# AJH_sup_marbles_v70.net
KiCad netlist of a schematic drawn in EAGLE
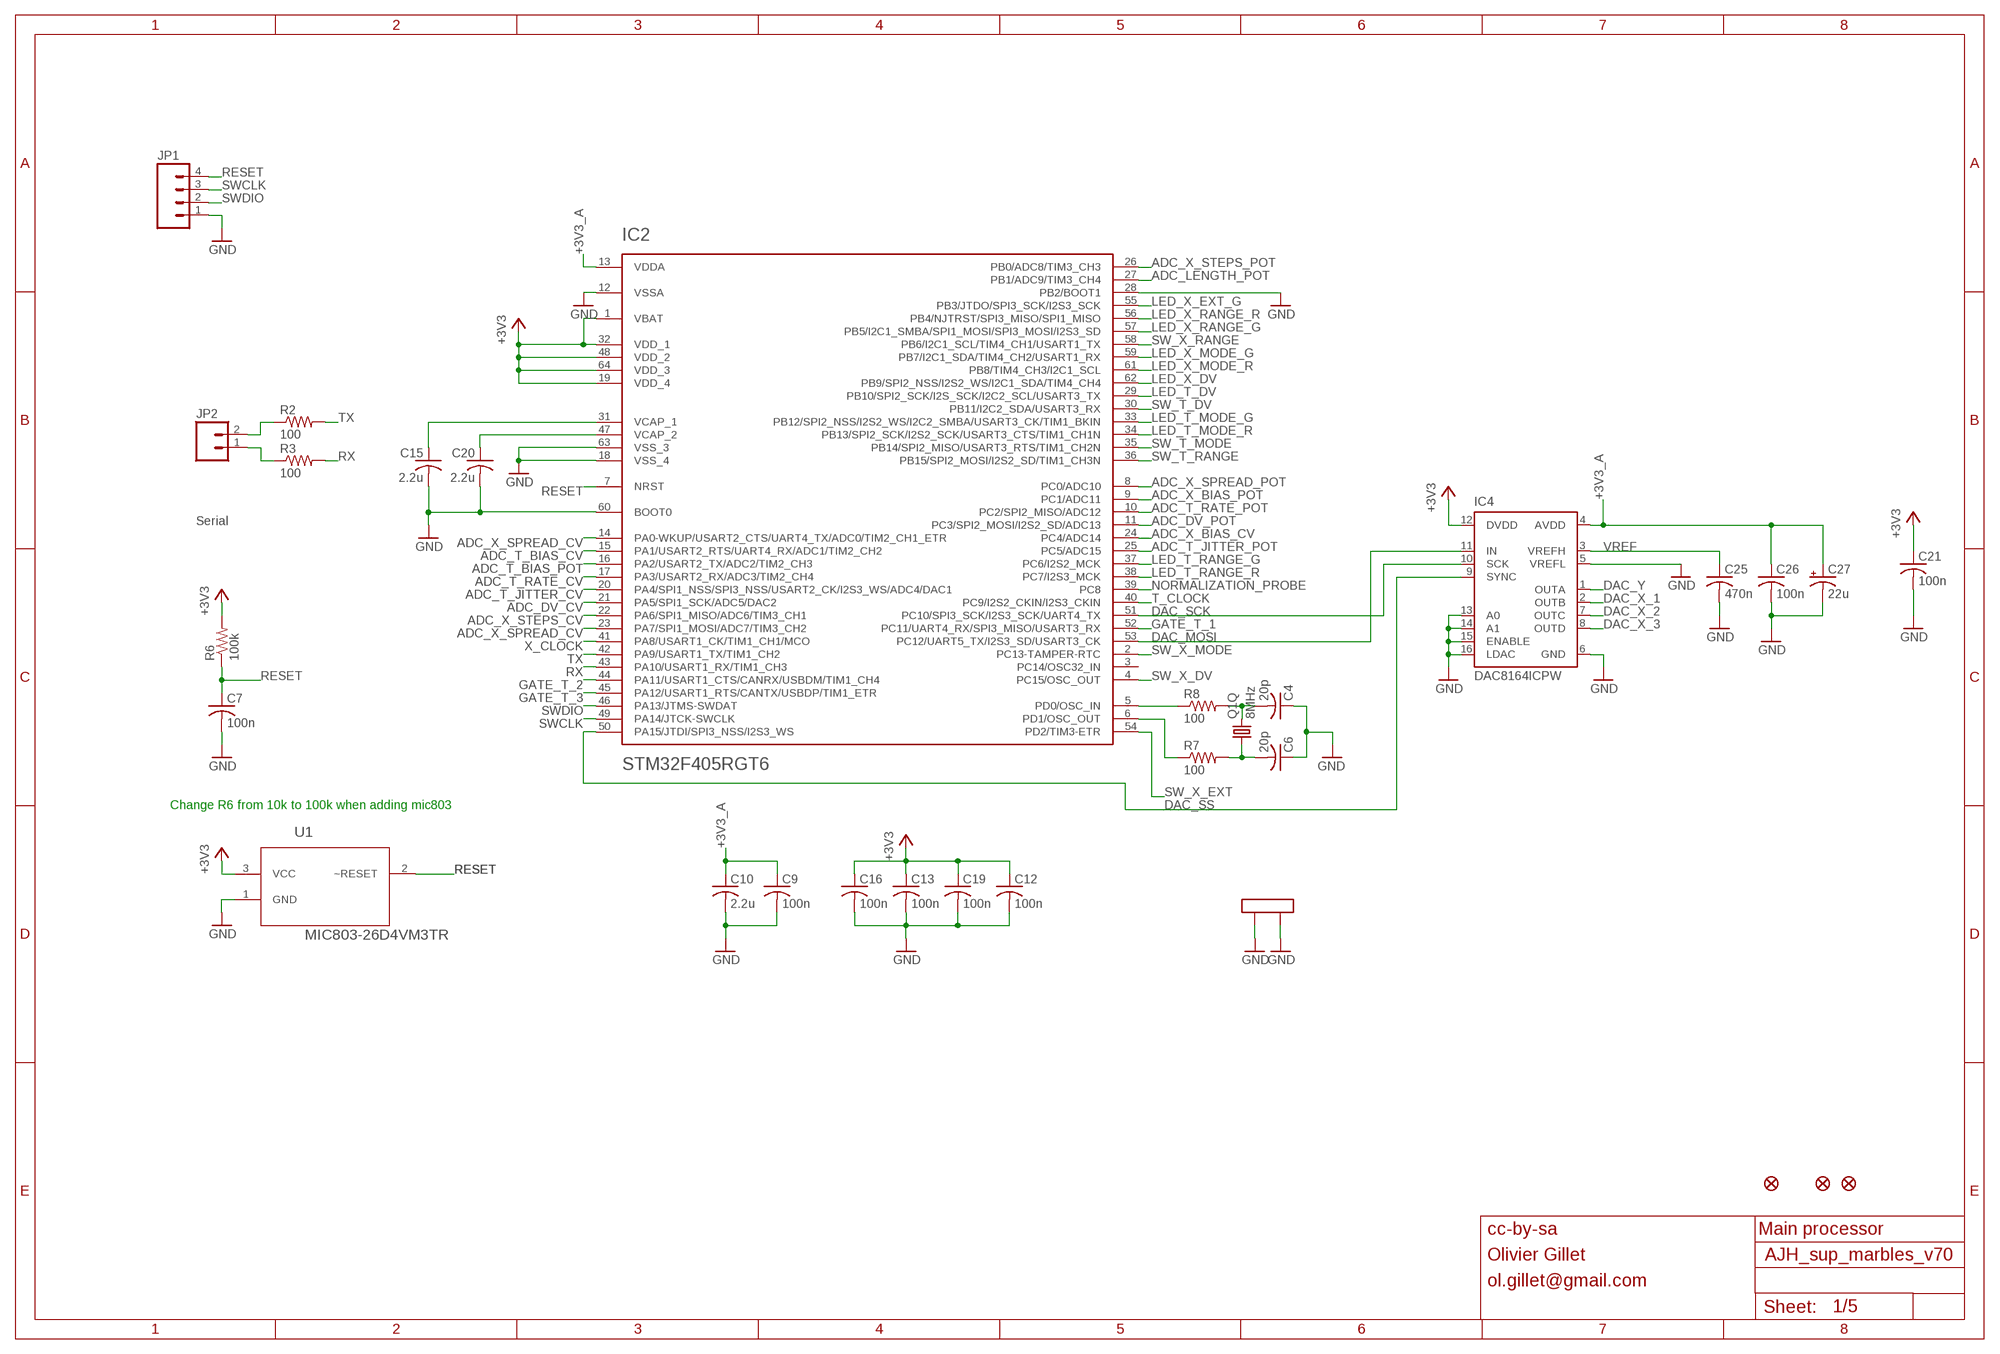
[diagram p0: schematic, sheet 1]
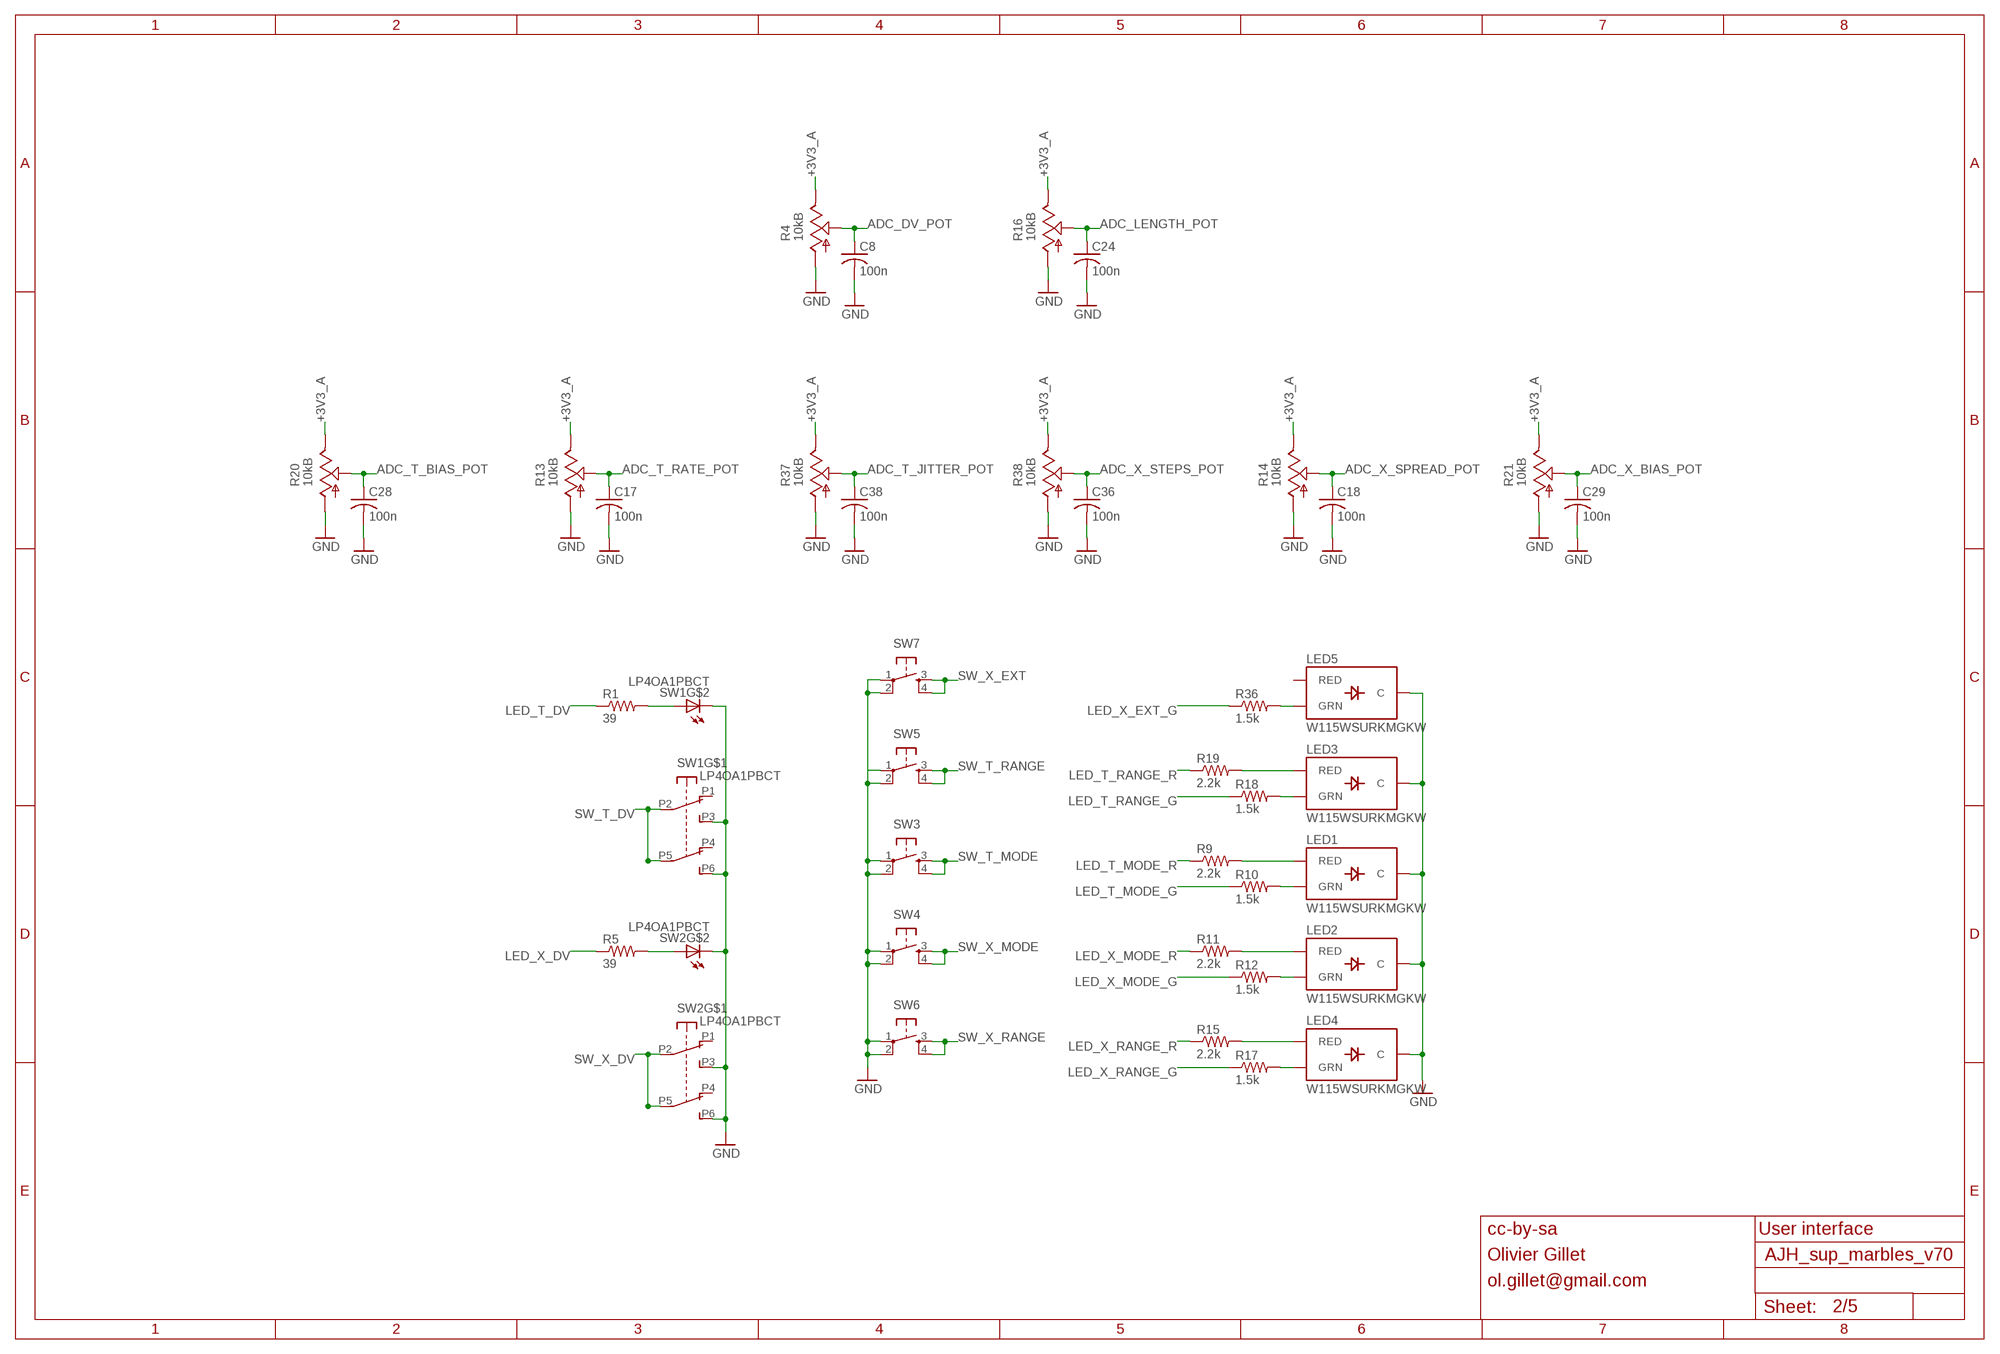
[diagram p1: schematic, sheet 2]
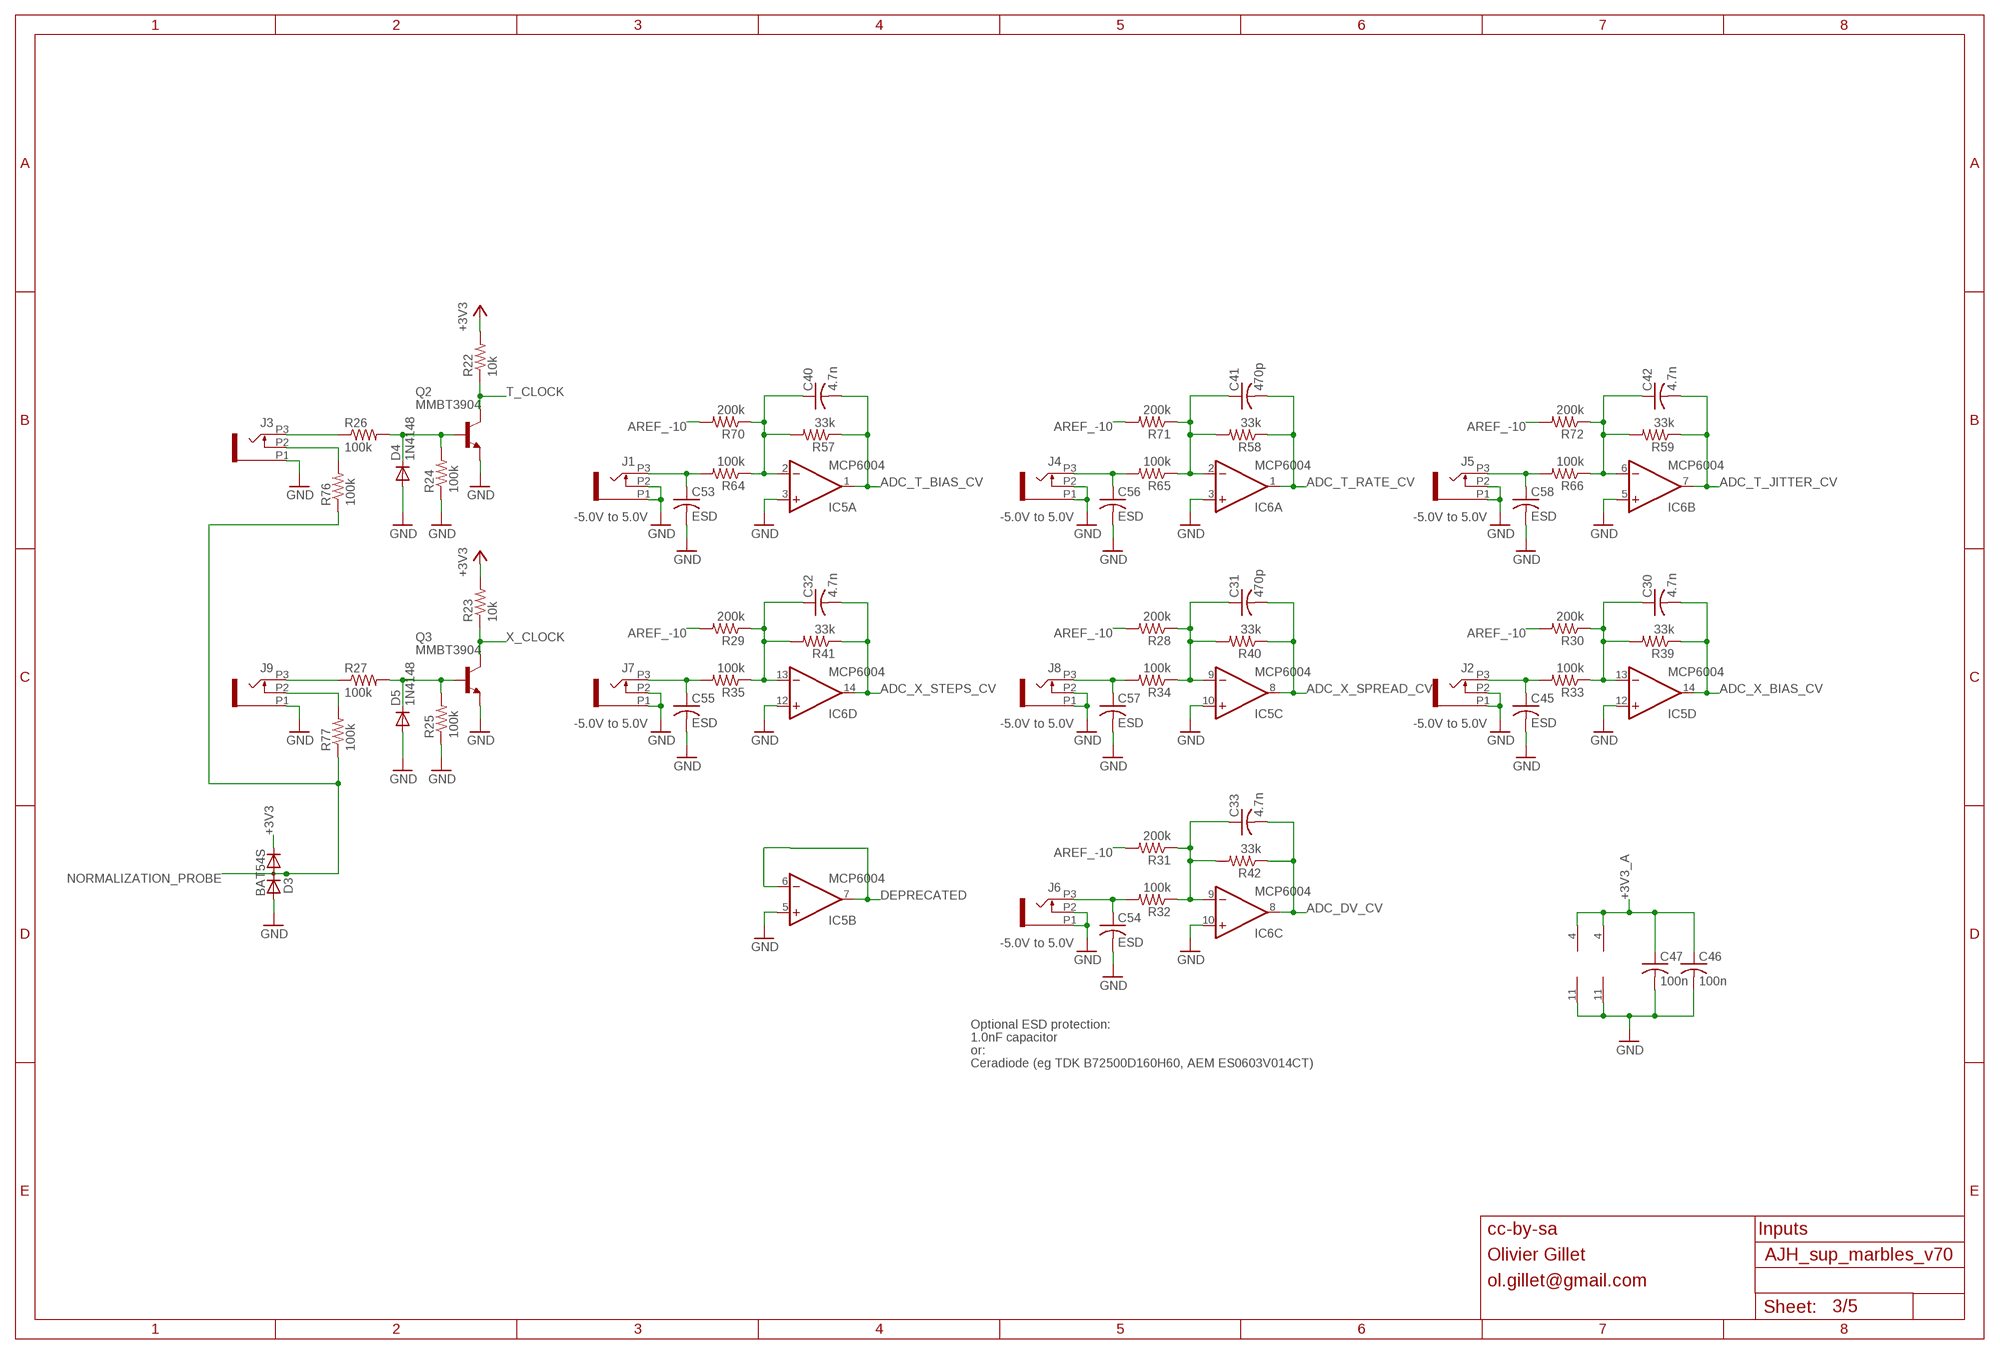
[diagram p2: schematic, sheet 3]
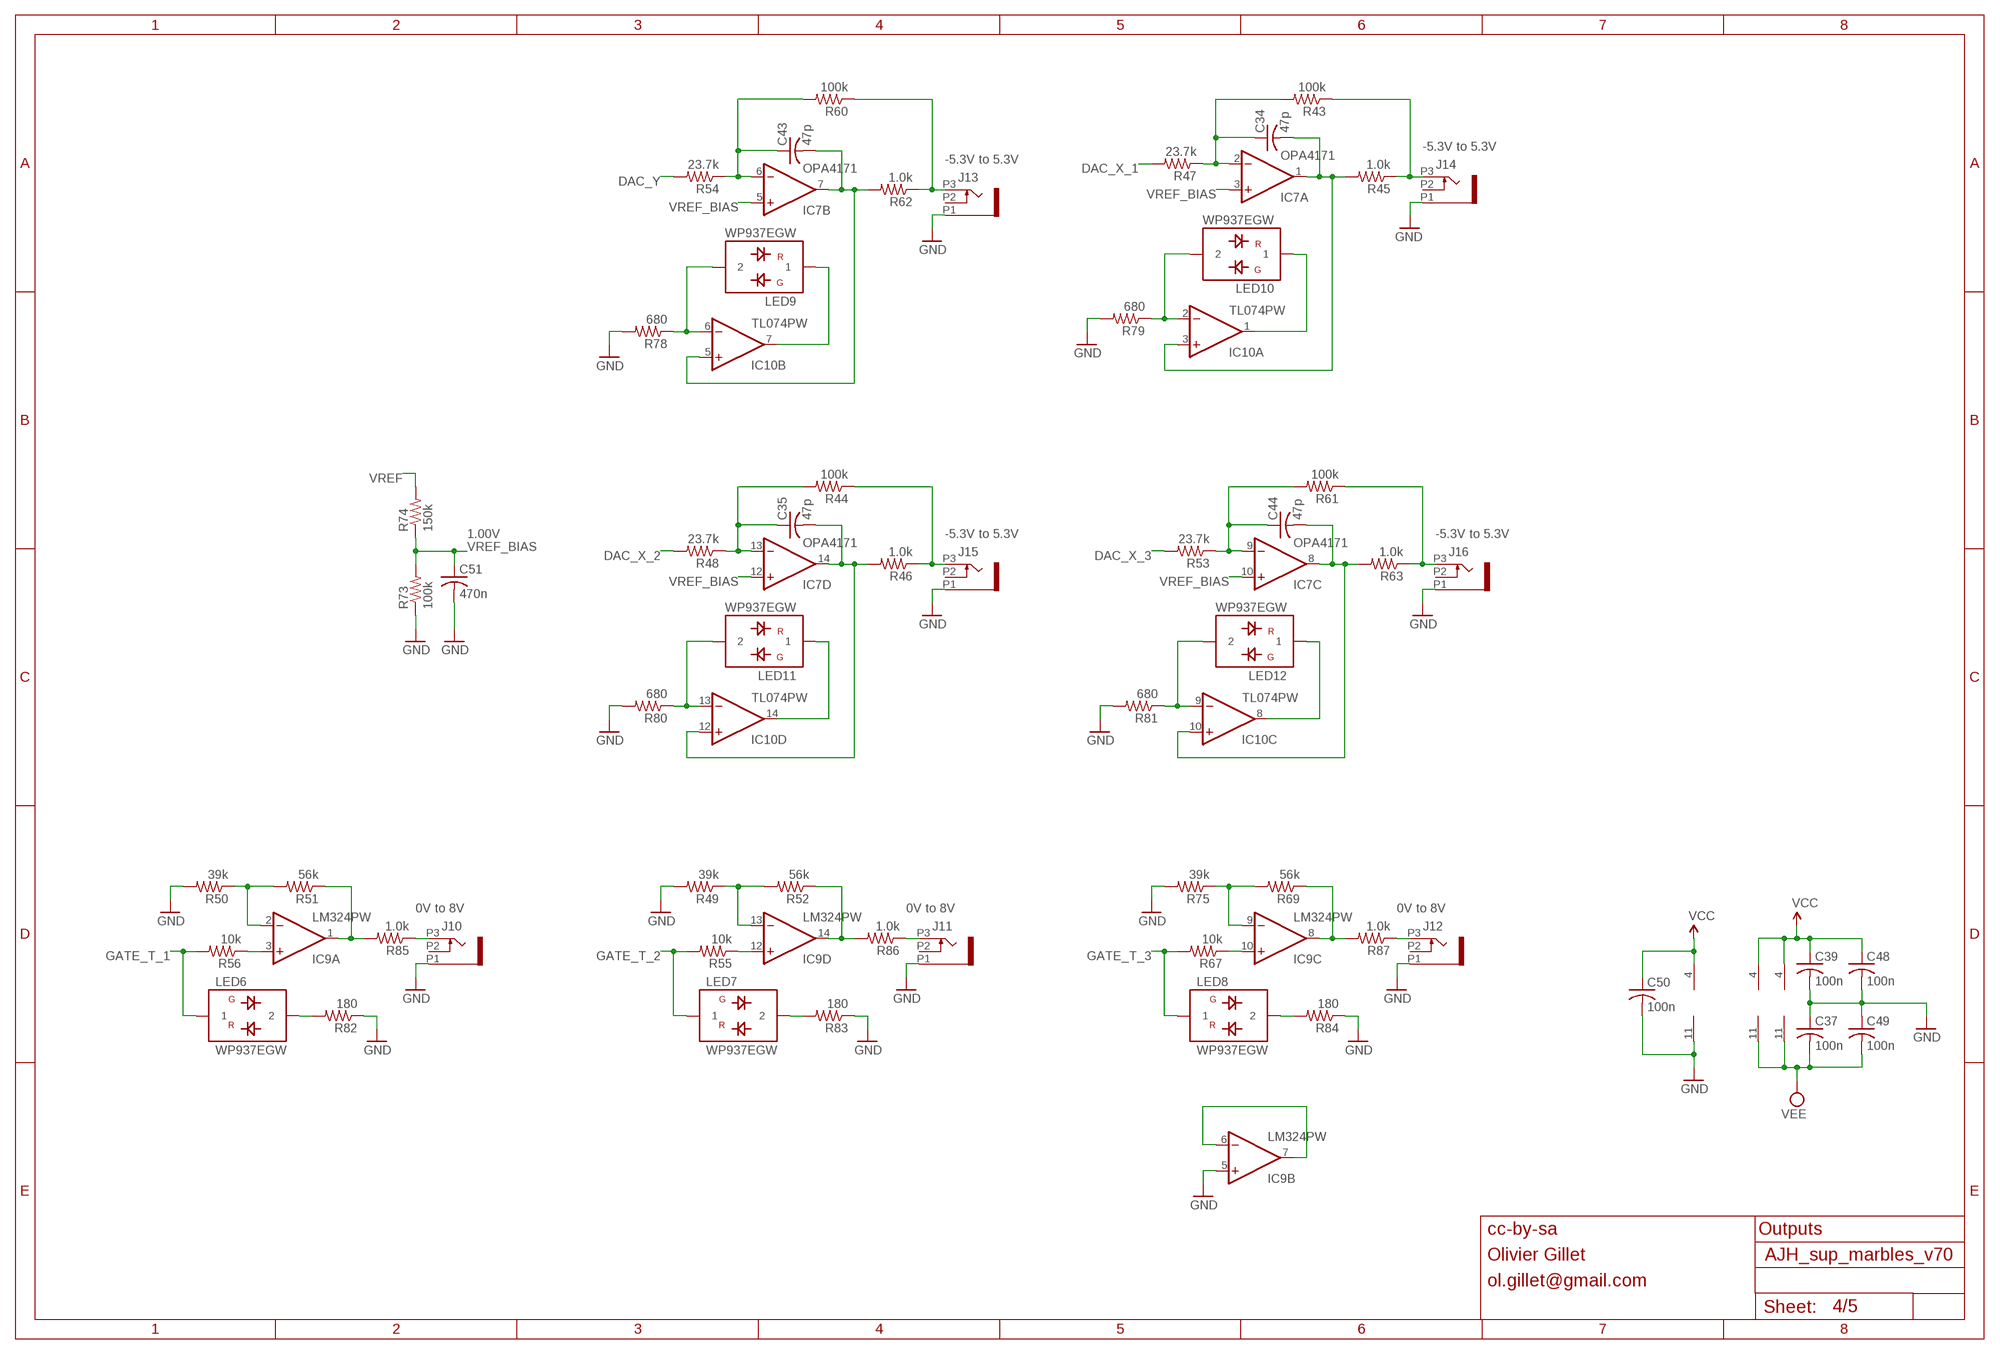
[diagram p3: schematic, sheet 4]
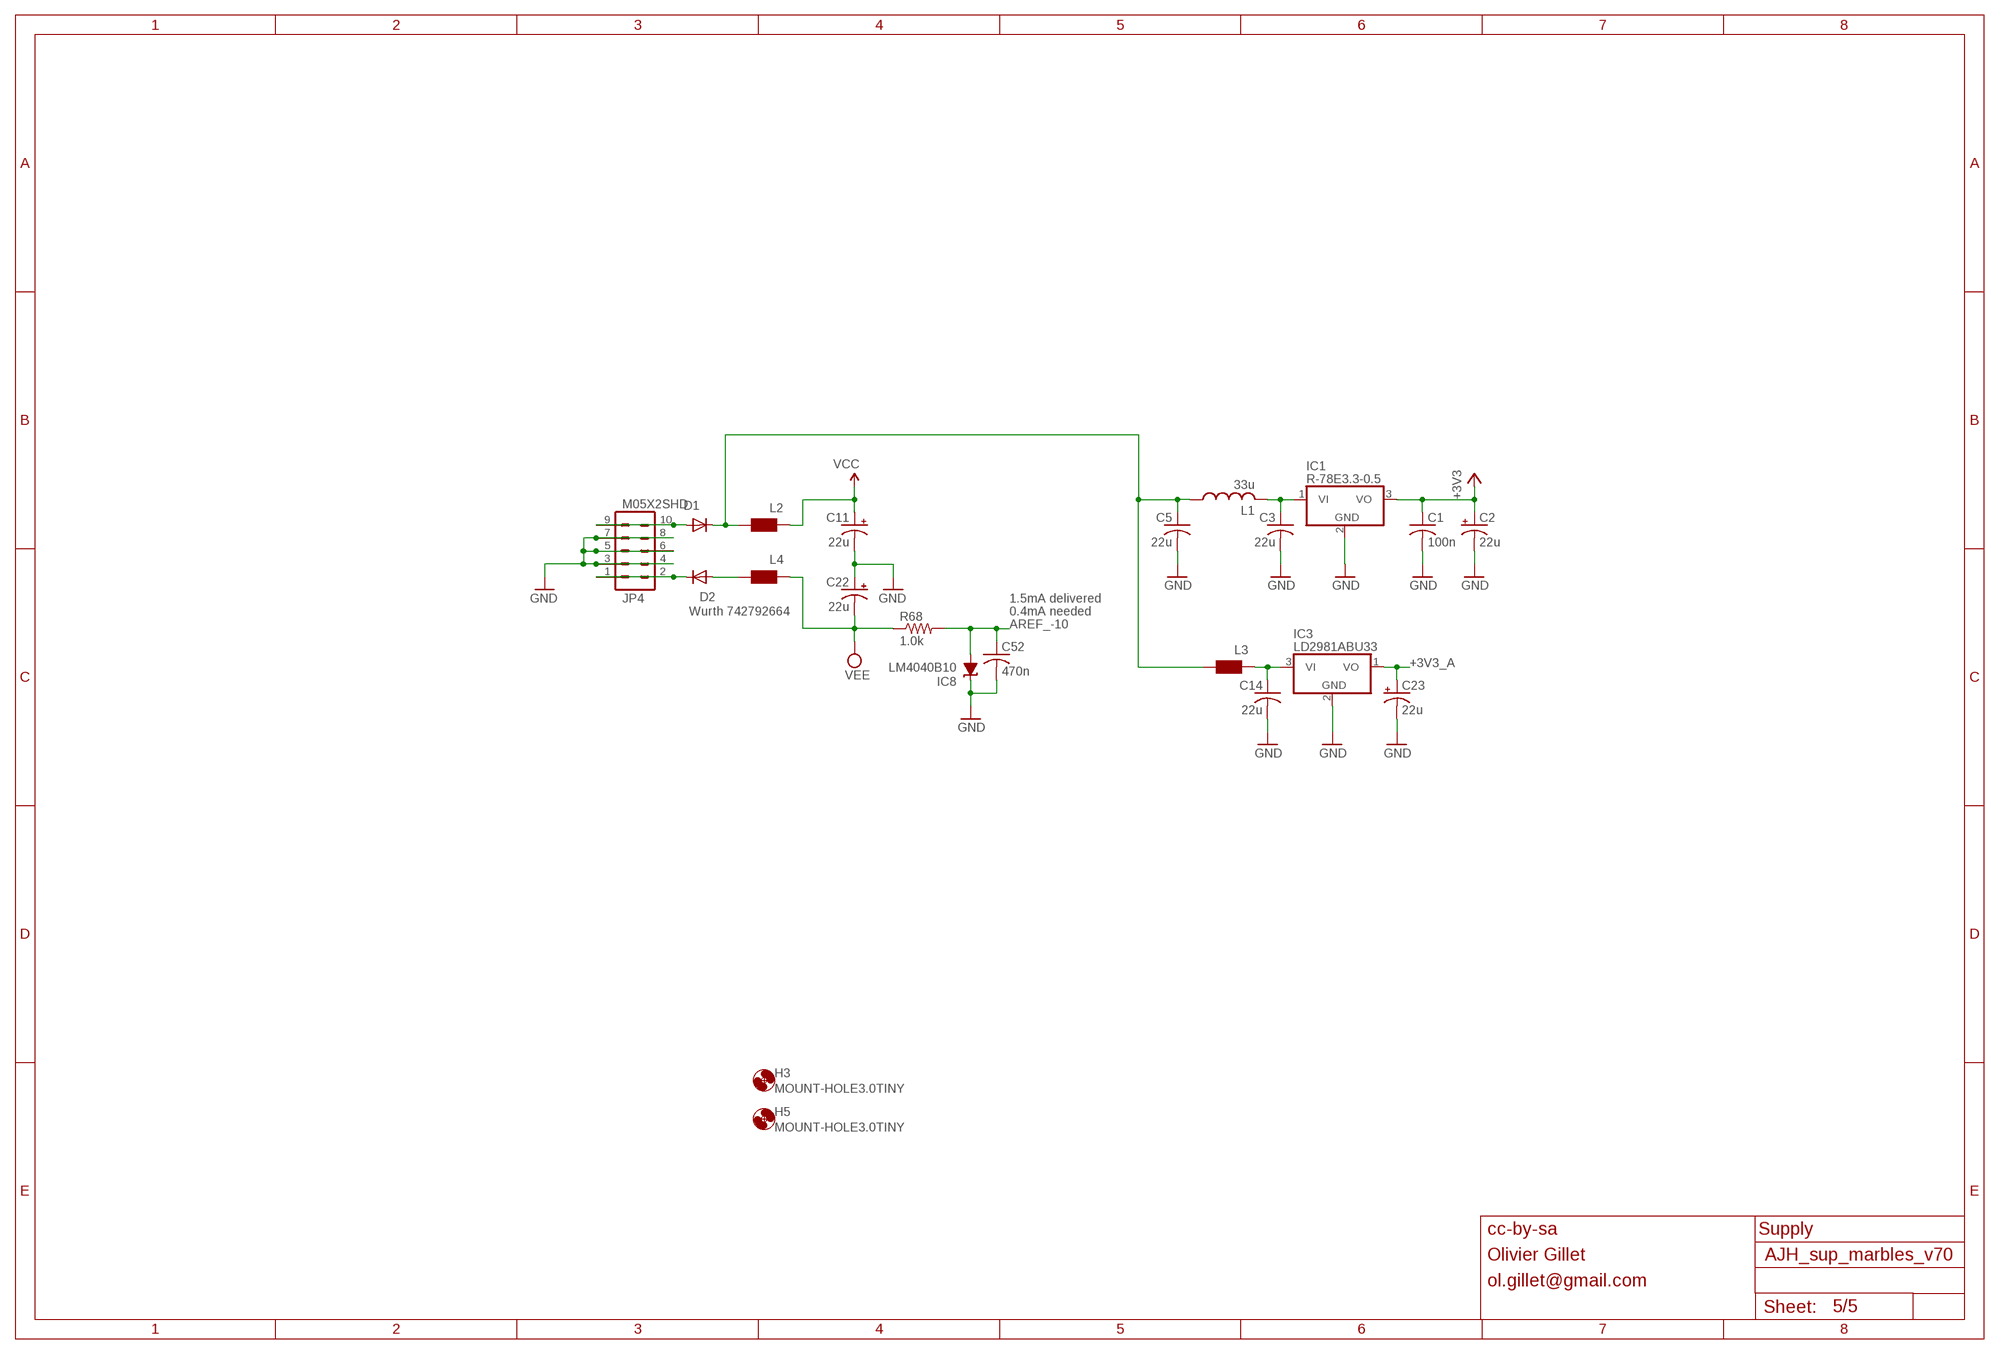
[diagram p4: schematic, sheet 5]

(export (version "E")
  (design (tool "Eeschema 10.0.6"))
  (components
    (comp (ref "C1")
      (value "100n")
      (footprint "eagle-import:C0402")
      (libsource (lib "eagle-import") (part "C-USC0402"))
    )
    (comp (ref "C2")
      (value "22u")
      (footprint "eagle-import:PANASONIC_C")
      (libsource (lib "eagle-import") (part "CPOL-USC"))
    )
    (comp (ref "C3")
      (value "22u")
      (footprint "eagle-import:C1206")
      (libsource (lib "eagle-import") (part "C-USC1206"))
    )
    (comp (ref "C5")
      (value "22u")
      (footprint "eagle-import:C1206")
      (libsource (lib "eagle-import") (part "C-USC1206"))
    )
    (comp (ref "C11")
      (value "22u")
      (footprint "eagle-import:PANASONIC_C")
      (libsource (lib "eagle-import") (part "CPOL-USC"))
    )
    (comp (ref "C14")
      (value "22u")
      (footprint "eagle-import:C1206")
      (libsource (lib "eagle-import") (part "C-USC1206"))
    )
    (comp (ref "C22")
      (value "22u")
      (footprint "eagle-import:PANASONIC_C")
      (libsource (lib "eagle-import") (part "CPOL-USC"))
    )
    (comp (ref "C23")
      (value "22u")
      (footprint "eagle-import:PANASONIC_C")
      (libsource (lib "eagle-import") (part "CPOL-USC"))
    )
    (comp (ref "C52")
      (value "470n")
      (footprint "eagle-import:C0402")
      (libsource (lib "eagle-import") (part "C-USC0402"))
    )
    (comp (ref "D1")
      (value "1N5819HW")
      (footprint "eagle-import:SOD123")
      (libsource (lib "eagle-import") (part "DIODE-SOD123"))
    )
    (comp (ref "D2")
      (value "1N5819HW")
      (footprint "eagle-import:SOD123")
      (libsource (lib "eagle-import") (part "DIODE-SOD123"))
    )
    (comp (ref "H3")
      (value "MOUNT-HOLE3.0TINY")
      (footprint "eagle-import:3,0TINY")
      (libsource (lib "eagle-import") (part "MOUNT-HOLE3.0TINY"))
    )
    (comp (ref "H5")
      (value "MOUNT-HOLE3.0TINY")
      (footprint "eagle-import:3,0TINY")
      (libsource (lib "eagle-import") (part "MOUNT-HOLE3.0TINY"))
    )
    (comp (ref "IC1")
      (value "R-78E3.3-0.5")
      (footprint "eagle-import:WE78")
      (libsource (lib "eagle-import") (part "WE173950378"))
    )
    (comp (ref "IC3")
      (value "LD2981ABU33")
      (footprint "eagle-import:SOT89")
      (libsource (lib "eagle-import") (part "LD2981ABU"))
    )
    (comp (ref "IC8")
      (value "LM4040B10")
      (footprint "eagle-import:DBZ_R-PDSO-G3")
      (libsource (lib "eagle-import") (part "LM4041DBZB12"))
    )
    (comp (ref "JP4")
      (value "M05X2SHD")
      (footprint "eagle-import:2X5-SHROUDED")
      (libsource (lib "eagle-import") (part "M05X2SHD"))
    )
    (comp (ref "L1")
      (value "33u")
      (footprint "eagle-import:L2012C")
      (libsource (lib "eagle-import") (part "L-USL2012C"))
    )
    (comp (ref "L2")
      (value "WE-CBF_0603")
      (footprint "eagle-import:0603")
      (libsource (lib "eagle-import") (part "WE-CBF_0603"))
    )
    (comp (ref "L3")
      (value "WE-CBF_0603")
      (footprint "eagle-import:0603")
      (libsource (lib "eagle-import") (part "WE-CBF_0603"))
    )
    (comp (ref "L4")
      (value "WE-CBF_0603")
      (footprint "eagle-import:0603")
      (libsource (lib "eagle-import") (part "WE-CBF_0603"))
    )
    (comp (ref "R68")
      (value "1.0k")
      (footprint "eagle-import:R0402")
      (libsource (lib "eagle-import") (part "R-US_R0402"))
    )
    (comp (ref "C4")
      (value "20p")
      (footprint "eagle-import:C0402")
      (libsource (lib "eagle-import") (part "C-USC0402"))
    )
    (comp (ref "C6")
      (value "20p")
      (footprint "eagle-import:C0402")
      (libsource (lib "eagle-import") (part "C-USC0402"))
    )
    (comp (ref "C7")
      (value "100n")
      (footprint "eagle-import:C0402")
      (libsource (lib "eagle-import") (part "C-USC0402"))
    )
    (comp (ref "C9")
      (value "100n")
      (footprint "eagle-import:C0402")
      (libsource (lib "eagle-import") (part "C-USC0402"))
    )
    (comp (ref "C10")
      (value "2.2u")
      (footprint "eagle-import:C0805")
      (libsource (lib "eagle-import") (part "C-USC0805"))
    )
    (comp (ref "C12")
      (value "100n")
      (footprint "eagle-import:C0402")
      (libsource (lib "eagle-import") (part "C-USC0402"))
    )
    (comp (ref "C13")
      (value "100n")
      (footprint "eagle-import:C0402")
      (libsource (lib "eagle-import") (part "C-USC0402"))
    )
    (comp (ref "C15")
      (value "2.2u")
      (footprint "eagle-import:C0805")
      (libsource (lib "eagle-import") (part "C-USC0805"))
    )
    (comp (ref "C16")
      (value "100n")
      (footprint "eagle-import:C0402")
      (libsource (lib "eagle-import") (part "C-USC0402"))
    )
    (comp (ref "C19")
      (value "100n")
      (footprint "eagle-import:C0402")
      (libsource (lib "eagle-import") (part "C-USC0402"))
    )
    (comp (ref "C20")
      (value "2.2u")
      (footprint "eagle-import:C0805")
      (libsource (lib "eagle-import") (part "C-USC0805"))
    )
    (comp (ref "C21")
      (value "100n")
      (footprint "eagle-import:C0402")
      (libsource (lib "eagle-import") (part "C-USC0402"))
    )
    (comp (ref "C25")
      (value "470n")
      (footprint "eagle-import:C0402")
      (libsource (lib "eagle-import") (part "C-USC0402"))
    )
    (comp (ref "C26")
      (value "100n")
      (footprint "eagle-import:C0402")
      (libsource (lib "eagle-import") (part "C-USC0402"))
    )
    (comp (ref "C27")
      (value "22u")
      (footprint "eagle-import:PANASONIC_C")
      (libsource (lib "eagle-import") (part "CPOL-USC"))
    )
    (comp (ref "F1")
      (value "FIDUCIAL1X2")
      (footprint "eagle-import:FIDUCIAL-1X2")
      (libsource (lib "eagle-import") (part "FIDUCIAL1X2"))
    )
    (comp (ref "F2")
      (value "FIDUCIAL1X2")
      (footprint "eagle-import:FIDUCIAL-1X2")
      (libsource (lib "eagle-import") (part "FIDUCIAL1X2"))
    )
    (comp (ref "F3")
      (value "FIDUCIAL1X2")
      (footprint "eagle-import:FIDUCIAL-1X2")
      (libsource (lib "eagle-import") (part "FIDUCIAL1X2"))
    )
    (comp (ref "IC2")
      (value "STM32F405RGT6")
      (footprint "eagle-import:TQFP-10X10-64")
      (libsource (lib "eagle-import") (part "STM32F20X"))
    )
    (comp (ref "IC4")
      (value "DAC8164ICPW")
      (footprint "eagle-import:SOP65P640X110-16N")
      (libsource (lib "eagle-import") (part "DAC8564"))
    )
    (comp (ref "JP1")
      (value "M04PTH")
      (footprint "eagle-import:1X04")
      (libsource (lib "eagle-import") (part "M04PTH"))
    )
    (comp (ref "JP2")
      (value "M02PTH")
      (footprint "eagle-import:1X02")
      (libsource (lib "eagle-import") (part "M02PTH"))
    )
    (comp (ref "Q1")
      (value "8MHz")
      (footprint "eagle-import:CTS406")
      (libsource (lib "eagle-import") (part "CRYSTAL"))
    )
    (comp (ref "R2")
      (value "100")
      (footprint "eagle-import:R0402")
      (libsource (lib "eagle-import") (part "R-US_R0402"))
    )
    (comp (ref "R3")
      (value "100")
      (footprint "eagle-import:R0402")
      (libsource (lib "eagle-import") (part "R-US_R0402"))
    )
    (comp (ref "R6")
      (value "100k")
      (footprint "eagle-import:R0402")
      (libsource (lib "eagle-import") (part "R-US_R0402"))
    )
    (comp (ref "R7")
      (value "100")
      (footprint "eagle-import:R0402")
      (libsource (lib "eagle-import") (part "R-US_R0402"))
    )
    (comp (ref "R8")
      (value "100")
      (footprint "eagle-import:R0402")
      (libsource (lib "eagle-import") (part "R-US_R0402"))
    )
    (comp (ref "U1")
      (value "MIC803-26D4VM3TR")
      (footprint "eagle-import:SOT95P232X110-3N")
      (libsource (lib "eagle-import") (part "MIC803-26D4VM3TR"))
    )
    (comp (ref "C8")
      (value "100n")
      (footprint "eagle-import:C0402")
      (libsource (lib "eagle-import") (part "C-USC0402"))
    )
    (comp (ref "C17")
      (value "100n")
      (footprint "eagle-import:C0402")
      (libsource (lib "eagle-import") (part "C-USC0402"))
    )
    (comp (ref "C18")
      (value "100n")
      (footprint "eagle-import:C0402")
      (libsource (lib "eagle-import") (part "C-USC0402"))
    )
    (comp (ref "C24")
      (value "100n")
      (footprint "eagle-import:C0402")
      (libsource (lib "eagle-import") (part "C-USC0402"))
    )
    (comp (ref "C28")
      (value "100n")
      (footprint "eagle-import:C0402")
      (libsource (lib "eagle-import") (part "C-USC0402"))
    )
    (comp (ref "C29")
      (value "100n")
      (footprint "eagle-import:C0402")
      (libsource (lib "eagle-import") (part "C-USC0402"))
    )
    (comp (ref "C36")
      (value "100n")
      (footprint "eagle-import:C0402")
      (libsource (lib "eagle-import") (part "C-USC0402"))
    )
    (comp (ref "C38")
      (value "100n")
      (footprint "eagle-import:C0402")
      (libsource (lib "eagle-import") (part "C-USC0402"))
    )
    (comp (ref "LED1")
      (value "W115WSURKMGKW")
      (footprint "eagle-import:LED-BICOLOR-THROUGHHOLE-2.54")
      (libsource (lib "eagle-import") (part "LED-BICOLOR-THROUGHHOLE2.54"))
    )
    (comp (ref "LED2")
      (value "W115WSURKMGKW")
      (footprint "eagle-import:LED-BICOLOR-THROUGHHOLE-2.54")
      (libsource (lib "eagle-import") (part "LED-BICOLOR-THROUGHHOLE2.54"))
    )
    (comp (ref "LED3")
      (value "W115WSURKMGKW")
      (footprint "eagle-import:LED-BICOLOR-THROUGHHOLE-2.54")
      (libsource (lib "eagle-import") (part "LED-BICOLOR-THROUGHHOLE2.54"))
    )
    (comp (ref "LED4")
      (value "W115WSURKMGKW")
      (footprint "eagle-import:LED-BICOLOR-THROUGHHOLE-2.54")
      (libsource (lib "eagle-import") (part "LED-BICOLOR-THROUGHHOLE2.54"))
    )
    (comp (ref "LED5")
      (value "W115WSURKMGKW")
      (footprint "eagle-import:LED-BICOLOR-THROUGHHOLE-2.54")
      (libsource (lib "eagle-import") (part "LED-BICOLOR-THROUGHHOLE2.54"))
    )
    (comp (ref "R1")
      (value "39")
      (footprint "eagle-import:R0402")
      (libsource (lib "eagle-import") (part "R-US_R0402"))
    )
    (comp (ref "R4")
      (value "10kB")
      (footprint "eagle-import:ALPS_POT_VERTICAL_PS")
      (libsource (lib "eagle-import") (part "POT_USVERTICAL_PS"))
    )
    (comp (ref "R5")
      (value "39")
      (footprint "eagle-import:R0402")
      (libsource (lib "eagle-import") (part "R-US_R0402"))
    )
    (comp (ref "R9")
      (value "2.2k")
      (footprint "eagle-import:R0402")
      (libsource (lib "eagle-import") (part "R-US_R0402"))
    )
    (comp (ref "R10")
      (value "1.5k")
      (footprint "eagle-import:R0402")
      (libsource (lib "eagle-import") (part "R-US_R0402"))
    )
    (comp (ref "R11")
      (value "2.2k")
      (footprint "eagle-import:R0402")
      (libsource (lib "eagle-import") (part "R-US_R0402"))
    )
    (comp (ref "R12")
      (value "1.5k")
      (footprint "eagle-import:R0402")
      (libsource (lib "eagle-import") (part "R-US_R0402"))
    )
    (comp (ref "R13")
      (value "10kB")
      (footprint "eagle-import:ALPS_POT_VERTICAL_PS")
      (libsource (lib "eagle-import") (part "POT_USVERTICAL_PS"))
    )
    (comp (ref "R14")
      (value "10kB")
      (footprint "eagle-import:ALPS_POT_VERTICAL_PS")
      (libsource (lib "eagle-import") (part "POT_USVERTICAL_PS"))
    )
    (comp (ref "R15")
      (value "2.2k")
      (footprint "eagle-import:R0402")
      (libsource (lib "eagle-import") (part "R-US_R0402"))
    )
    (comp (ref "R16")
      (value "10kB")
      (footprint "eagle-import:ALPS_POT_VERTICAL_PS")
      (libsource (lib "eagle-import") (part "POT_USVERTICAL_PS"))
    )
    (comp (ref "R17")
      (value "1.5k")
      (footprint "eagle-import:R0402")
      (libsource (lib "eagle-import") (part "R-US_R0402"))
    )
    (comp (ref "R18")
      (value "1.5k")
      (footprint "eagle-import:R0402")
      (libsource (lib "eagle-import") (part "R-US_R0402"))
    )
    (comp (ref "R19")
      (value "2.2k")
      (footprint "eagle-import:R0402")
      (libsource (lib "eagle-import") (part "R-US_R0402"))
    )
    (comp (ref "R20")
      (value "10kB")
      (footprint "eagle-import:ALPS_POT_VERTICAL_PS")
      (libsource (lib "eagle-import") (part "POT_USVERTICAL_PS"))
    )
    (comp (ref "R21")
      (value "10kB")
      (footprint "eagle-import:ALPS_POT_VERTICAL_PS")
      (libsource (lib "eagle-import") (part "POT_USVERTICAL_PS"))
    )
    (comp (ref "R36")
      (value "1.5k")
      (footprint "eagle-import:R0402")
      (libsource (lib "eagle-import") (part "R-US_R0402"))
    )
    (comp (ref "R37")
      (value "10kB")
      (footprint "eagle-import:ALPS_POT_VERTICAL_PS")
      (libsource (lib "eagle-import") (part "POT_USVERTICAL_PS"))
    )
    (comp (ref "R38")
      (value "10kB")
      (footprint "eagle-import:ALPS_POT_VERTICAL_PS")
      (libsource (lib "eagle-import") (part "POT_USVERTICAL_PS"))
    )
    (comp (ref "SW1")
      (value "LP4OA1PBCT")
      (footprint "eagle-import:LP4OA1PBCT")
      (libsource (lib "eagle-import") (part "LP4OA1PBCT"))
    )
    (comp (ref "SW2")
      (value "LP4OA1PBCT")
      (footprint "eagle-import:LP4OA1PBCT")
      (libsource (lib "eagle-import") (part "LP4OA1PBCT"))
    )
    (comp (ref "SW3")
      (value "TAC_SWITCHPTH")
      (footprint "eagle-import:TACTILE-PTH")
      (libsource (lib "eagle-import") (part "TAC_SWITCHPTH"))
    )
    (comp (ref "SW4")
      (value "TAC_SWITCHPTH")
      (footprint "eagle-import:TACTILE-PTH")
      (libsource (lib "eagle-import") (part "TAC_SWITCHPTH"))
    )
    (comp (ref "SW5")
      (value "TAC_SWITCHPTH")
      (footprint "eagle-import:TACTILE-PTH")
      (libsource (lib "eagle-import") (part "TAC_SWITCHPTH"))
    )
    (comp (ref "SW6")
      (value "TAC_SWITCHPTH")
      (footprint "eagle-import:TACTILE-PTH")
      (libsource (lib "eagle-import") (part "TAC_SWITCHPTH"))
    )
    (comp (ref "SW7")
      (value "TAC_SWITCHPTH")
      (footprint "eagle-import:TACTILE-PTH")
      (libsource (lib "eagle-import") (part "TAC_SWITCHPTH"))
    )
    (comp (ref "C34")
      (value "47p")
      (footprint "eagle-import:C0402")
      (libsource (lib "eagle-import") (part "C-USC0402"))
    )
    (comp (ref "C35")
      (value "47p")
      (footprint "eagle-import:C0402")
      (libsource (lib "eagle-import") (part "C-USC0402"))
    )
    (comp (ref "C37")
      (value "100n")
      (footprint "eagle-import:C0402")
      (libsource (lib "eagle-import") (part "C-USC0402"))
    )
    (comp (ref "C39")
      (value "100n")
      (footprint "eagle-import:C0402")
      (libsource (lib "eagle-import") (part "C-USC0402"))
    )
    (comp (ref "C43")
      (value "47p")
      (footprint "eagle-import:C0402")
      (libsource (lib "eagle-import") (part "C-USC0402"))
    )
    (comp (ref "C44")
      (value "47p")
      (footprint "eagle-import:C0402")
      (libsource (lib "eagle-import") (part "C-USC0402"))
    )
    (comp (ref "C48")
      (value "100n")
      (footprint "eagle-import:C0402")
      (libsource (lib "eagle-import") (part "C-USC0402"))
    )
    (comp (ref "C49")
      (value "100n")
      (footprint "eagle-import:C0402")
      (libsource (lib "eagle-import") (part "C-USC0402"))
    )
    (comp (ref "C50")
      (value "100n")
      (footprint "eagle-import:C0402")
      (libsource (lib "eagle-import") (part "C-USC0402"))
    )
    (comp (ref "C51")
      (value "470n")
      (footprint "eagle-import:C0402")
      (libsource (lib "eagle-import") (part "C-USC0402"))
    )
    (comp (ref "IC7")
      (value "OPA4171")
      (footprint "eagle-import:TSSOP14_065")
      (libsource (lib "eagle-import") (part "TL074PW"))
    )
    (comp (ref "IC9")
      (value "LM324PW")
      (footprint "eagle-import:TSSOP14_065")
      (libsource (lib "eagle-import") (part "TL074PW"))
    )
    (comp (ref "IC10")
      (value "TL074PW")
      (footprint "eagle-import:TSSOP14_065")
      (libsource (lib "eagle-import") (part "TL074PW"))
    )
    (comp (ref "J10")
      (value "PJ301_THONKICONN6")
      (footprint "eagle-import:WQP_PJ_301M6")
      (libsource (lib "eagle-import") (part "PJ301_THONKICONN6"))
    )
    (comp (ref "J11")
      (value "PJ301_THONKICONN6")
      (footprint "eagle-import:WQP_PJ_301M6")
      (libsource (lib "eagle-import") (part "PJ301_THONKICONN6"))
    )
    (comp (ref "J12")
      (value "PJ301_THONKICONN6")
      (footprint "eagle-import:WQP_PJ_301M6")
      (libsource (lib "eagle-import") (part "PJ301_THONKICONN6"))
    )
    (comp (ref "J13")
      (value "PJ301_THONKICONN6")
      (footprint "eagle-import:WQP_PJ_301M6")
      (libsource (lib "eagle-import") (part "PJ301_THONKICONN6"))
    )
    (comp (ref "J14")
      (value "PJ301_THONKICONN6")
      (footprint "eagle-import:WQP_PJ_301M6")
      (libsource (lib "eagle-import") (part "PJ301_THONKICONN6"))
    )
    (comp (ref "J15")
      (value "PJ301_THONKICONN6")
      (footprint "eagle-import:WQP_PJ_301M6")
      (libsource (lib "eagle-import") (part "PJ301_THONKICONN6"))
    )
    (comp (ref "J16")
      (value "PJ301_THONKICONN6")
      (footprint "eagle-import:WQP_PJ_301M6")
      (libsource (lib "eagle-import") (part "PJ301_THONKICONN6"))
    )
    (comp (ref "LED6")
      (value "WP937EGW")
      (footprint "eagle-import:LED3MM")
      (libsource (lib "eagle-import") (part "LED-BICOLOR-SHARED-THROUGHHOLE"))
    )
    (comp (ref "LED7")
      (value "WP937EGW")
      (footprint "eagle-import:LED3MM")
      (libsource (lib "eagle-import") (part "LED-BICOLOR-SHARED-THROUGHHOLE"))
    )
    (comp (ref "LED8")
      (value "WP937EGW")
      (footprint "eagle-import:LED3MM")
      (libsource (lib "eagle-import") (part "LED-BICOLOR-SHARED-THROUGHHOLE"))
    )
    (comp (ref "LED9")
      (value "WP937EGW")
      (footprint "eagle-import:LED3MM")
      (libsource (lib "eagle-import") (part "LED-BICOLOR-SHARED-THROUGHHOLE"))
    )
    (comp (ref "LED10")
      (value "WP937EGW")
      (footprint "eagle-import:LED3MM")
      (libsource (lib "eagle-import") (part "LED-BICOLOR-SHARED-THROUGHHOLE"))
    )
    (comp (ref "LED11")
      (value "WP937EGW")
      (footprint "eagle-import:LED3MM")
      (libsource (lib "eagle-import") (part "LED-BICOLOR-SHARED-THROUGHHOLE"))
    )
    (comp (ref "LED12")
      (value "WP937EGW")
      (footprint "eagle-import:LED3MM")
      (libsource (lib "eagle-import") (part "LED-BICOLOR-SHARED-THROUGHHOLE"))
    )
    (comp (ref "R43")
      (value "100k")
      (footprint "eagle-import:R0402")
      (libsource (lib "eagle-import") (part "R-US_R0402"))
    )
    (comp (ref "R44")
      (value "100k")
      (footprint "eagle-import:R0402")
      (libsource (lib "eagle-import") (part "R-US_R0402"))
    )
    (comp (ref "R45")
      (value "1.0k")
      (footprint "eagle-import:R0603")
      (libsource (lib "eagle-import") (part "R-US_R0603"))
    )
    (comp (ref "R46")
      (value "1.0k")
      (footprint "eagle-import:R0603")
      (libsource (lib "eagle-import") (part "R-US_R0603"))
    )
    (comp (ref "R47")
      (value "23.7k")
      (footprint "eagle-import:R0402")
      (libsource (lib "eagle-import") (part "R-US_R0402"))
    )
    (comp (ref "R48")
      (value "23.7k")
      (footprint "eagle-import:R0402")
      (libsource (lib "eagle-import") (part "R-US_R0402"))
    )
    (comp (ref "R49")
      (value "39k")
      (footprint "eagle-import:R0402")
      (libsource (lib "eagle-import") (part "R-US_R0402"))
    )
    (comp (ref "R50")
      (value "39k")
      (footprint "eagle-import:R0402")
      (libsource (lib "eagle-import") (part "R-US_R0402"))
    )
    (comp (ref "R51")
      (value "56k")
      (footprint "eagle-import:R0402")
      (libsource (lib "eagle-import") (part "R-US_R0402"))
    )
    (comp (ref "R52")
      (value "56k")
      (footprint "eagle-import:R0402")
      (libsource (lib "eagle-import") (part "R-US_R0402"))
    )
    (comp (ref "R53")
      (value "23.7k")
      (footprint "eagle-import:R0402")
      (libsource (lib "eagle-import") (part "R-US_R0402"))
    )
    (comp (ref "R54")
      (value "23.7k")
      (footprint "eagle-import:R0402")
      (libsource (lib "eagle-import") (part "R-US_R0402"))
    )
    (comp (ref "R55")
      (value "10k")
      (footprint "eagle-import:R0402")
      (libsource (lib "eagle-import") (part "R-US_R0402"))
    )
    (comp (ref "R56")
      (value "10k")
      (footprint "eagle-import:R0402")
      (libsource (lib "eagle-import") (part "R-US_R0402"))
    )
    (comp (ref "R60")
      (value "100k")
      (footprint "eagle-import:R0402")
      (libsource (lib "eagle-import") (part "R-US_R0402"))
    )
    (comp (ref "R61")
      (value "100k")
      (footprint "eagle-import:R0402")
      (libsource (lib "eagle-import") (part "R-US_R0402"))
    )
    (comp (ref "R62")
      (value "1.0k")
      (footprint "eagle-import:R0603")
      (libsource (lib "eagle-import") (part "R-US_R0603"))
    )
    (comp (ref "R63")
      (value "1.0k")
      (footprint "eagle-import:R0603")
      (libsource (lib "eagle-import") (part "R-US_R0603"))
    )
    (comp (ref "R67")
      (value "10k")
      (footprint "eagle-import:R0402")
      (libsource (lib "eagle-import") (part "R-US_R0402"))
    )
    (comp (ref "R69")
      (value "56k")
      (footprint "eagle-import:R0402")
      (libsource (lib "eagle-import") (part "R-US_R0402"))
    )
    (comp (ref "R73")
      (value "100k")
      (footprint "eagle-import:R0402")
      (libsource (lib "eagle-import") (part "R-US_R0402"))
    )
    (comp (ref "R74")
      (value "150k")
      (footprint "eagle-import:R0402")
      (libsource (lib "eagle-import") (part "R-US_R0402"))
    )
    (comp (ref "R75")
      (value "39k")
      (footprint "eagle-import:R0402")
      (libsource (lib "eagle-import") (part "R-US_R0402"))
    )
    (comp (ref "R78")
      (value "680")
      (footprint "eagle-import:R0402")
      (libsource (lib "eagle-import") (part "R-US_R0402"))
    )
    (comp (ref "R79")
      (value "680")
      (footprint "eagle-import:R0402")
      (libsource (lib "eagle-import") (part "R-US_R0402"))
    )
    (comp (ref "R80")
      (value "680")
      (footprint "eagle-import:R0402")
      (libsource (lib "eagle-import") (part "R-US_R0402"))
    )
    (comp (ref "R81")
      (value "680")
      (footprint "eagle-import:R0402")
      (libsource (lib "eagle-import") (part "R-US_R0402"))
    )
    (comp (ref "R82")
      (value "180")
      (footprint "eagle-import:R0402")
      (libsource (lib "eagle-import") (part "R-US_R0402"))
    )
    (comp (ref "R83")
      (value "180")
      (footprint "eagle-import:R0402")
      (libsource (lib "eagle-import") (part "R-US_R0402"))
    )
    (comp (ref "R84")
      (value "180")
      (footprint "eagle-import:R0402")
      (libsource (lib "eagle-import") (part "R-US_R0402"))
    )
    (comp (ref "R85")
      (value "1.0k")
      (footprint "eagle-import:R0603")
      (libsource (lib "eagle-import") (part "R-US_R0603"))
    )
    (comp (ref "R86")
      (value "1.0k")
      (footprint "eagle-import:R0603")
      (libsource (lib "eagle-import") (part "R-US_R0603"))
    )
    (comp (ref "R87")
      (value "1.0k")
      (footprint "eagle-import:R0603")
      (libsource (lib "eagle-import") (part "R-US_R0603"))
    )
    (comp (ref "C30")
      (value "4.7n")
      (footprint "eagle-import:C0402")
      (libsource (lib "eagle-import") (part "C-USC0402"))
    )
    (comp (ref "C31")
      (value "470p")
      (footprint "eagle-import:C0402")
      (libsource (lib "eagle-import") (part "C-USC0402"))
    )
    (comp (ref "C32")
      (value "4.7n")
      (footprint "eagle-import:C0402")
      (libsource (lib "eagle-import") (part "C-USC0402"))
    )
    (comp (ref "C33")
      (value "4.7n")
      (footprint "eagle-import:C0402")
      (libsource (lib "eagle-import") (part "C-USC0402"))
    )
    (comp (ref "C40")
      (value "4.7n")
      (footprint "eagle-import:C0402")
      (libsource (lib "eagle-import") (part "C-USC0402"))
    )
    (comp (ref "C41")
      (value "470p")
      (footprint "eagle-import:C0402")
      (libsource (lib "eagle-import") (part "C-USC0402"))
    )
    (comp (ref "C42")
      (value "4.7n")
      (footprint "eagle-import:C0402")
      (libsource (lib "eagle-import") (part "C-USC0402"))
    )
    (comp (ref "C45")
      (value "ESD")
      (footprint "eagle-import:C0603")
      (libsource (lib "eagle-import") (part "C-USC0603"))
    )
    (comp (ref "C46")
      (value "100n")
      (footprint "eagle-import:C0402")
      (libsource (lib "eagle-import") (part "C-USC0402"))
    )
    (comp (ref "C47")
      (value "100n")
      (footprint "eagle-import:C0402")
      (libsource (lib "eagle-import") (part "C-USC0402"))
    )
    (comp (ref "C53")
      (value "ESD")
      (footprint "eagle-import:C0603")
      (libsource (lib "eagle-import") (part "C-USC0603"))
    )
    (comp (ref "C54")
      (value "ESD")
      (footprint "eagle-import:C0603")
      (libsource (lib "eagle-import") (part "C-USC0603"))
    )
    (comp (ref "C55")
      (value "ESD")
      (footprint "eagle-import:C0603")
      (libsource (lib "eagle-import") (part "C-USC0603"))
    )
    (comp (ref "C56")
      (value "ESD")
      (footprint "eagle-import:C0603")
      (libsource (lib "eagle-import") (part "C-USC0603"))
    )
    (comp (ref "C57")
      (value "ESD")
      (footprint "eagle-import:C0603")
      (libsource (lib "eagle-import") (part "C-USC0603"))
    )
    (comp (ref "C58")
      (value "ESD")
      (footprint "eagle-import:C0603")
      (libsource (lib "eagle-import") (part "C-USC0603"))
    )
    (comp (ref "D3")
      (value "BAT54S")
      (footprint "eagle-import:SOT23")
      (libsource (lib "eagle-import") (part "DIODE_2CACA-SOT23"))
    )
    (comp (ref "D4")
      (value "1N4148")
      (footprint "eagle-import:SOD523")
      (libsource (lib "eagle-import") (part "DIODE-SOD523"))
    )
    (comp (ref "D5")
      (value "1N4148")
      (footprint "eagle-import:SOD523")
      (libsource (lib "eagle-import") (part "DIODE-SOD523"))
    )
    (comp (ref "IC5")
      (value "MCP6004")
      (footprint "eagle-import:TSSOP14_065")
      (libsource (lib "eagle-import") (part "TL074PW"))
    )
    (comp (ref "IC6")
      (value "MCP6004")
      (footprint "eagle-import:TSSOP14_065")
      (libsource (lib "eagle-import") (part "TL074PW"))
    )
    (comp (ref "J1")
      (value "PJ301_THONKICONN6")
      (footprint "eagle-import:WQP_PJ_301M6")
      (libsource (lib "eagle-import") (part "PJ301_THONKICONN6"))
    )
    (comp (ref "J2")
      (value "PJ301_THONKICONN6")
      (footprint "eagle-import:WQP_PJ_301M6")
      (libsource (lib "eagle-import") (part "PJ301_THONKICONN6"))
    )
    (comp (ref "J3")
      (value "PJ301_THONKICONN6")
      (footprint "eagle-import:WQP_PJ_301M6")
      (libsource (lib "eagle-import") (part "PJ301_THONKICONN6"))
    )
    (comp (ref "J4")
      (value "PJ301_THONKICONN6")
      (footprint "eagle-import:WQP_PJ_301M6")
      (libsource (lib "eagle-import") (part "PJ301_THONKICONN6"))
    )
    (comp (ref "J5")
      (value "PJ301_THONKICONN6")
      (footprint "eagle-import:WQP_PJ_301M6")
      (libsource (lib "eagle-import") (part "PJ301_THONKICONN6"))
    )
    (comp (ref "J6")
      (value "PJ301_THONKICONN6")
      (footprint "eagle-import:WQP_PJ_301M6")
      (libsource (lib "eagle-import") (part "PJ301_THONKICONN6"))
    )
    (comp (ref "J7")
      (value "PJ301_THONKICONN6")
      (footprint "eagle-import:WQP_PJ_301M6")
      (libsource (lib "eagle-import") (part "PJ301_THONKICONN6"))
    )
    (comp (ref "J8")
      (value "PJ301_THONKICONN6")
      (footprint "eagle-import:WQP_PJ_301M6")
      (libsource (lib "eagle-import") (part "PJ301_THONKICONN6"))
    )
    (comp (ref "J9")
      (value "PJ301_THONKICONN6")
      (footprint "eagle-import:WQP_PJ_301M6")
      (libsource (lib "eagle-import") (part "PJ301_THONKICONN6"))
    )
    (comp (ref "Q2")
      (value "MMBT3904")
      (footprint "eagle-import:SOT23-BEC")
      (libsource (lib "eagle-import") (part "-NPN-SOT23-BECMMBT3904LT1"))
    )
    (comp (ref "Q3")
      (value "MMBT3904")
      (footprint "eagle-import:SOT23-BEC")
      (libsource (lib "eagle-import") (part "-NPN-SOT23-BECMMBT3904LT1"))
    )
    (comp (ref "R22")
      (value "10k")
      (footprint "eagle-import:R0402")
      (libsource (lib "eagle-import") (part "R-US_R0402"))
    )
    (comp (ref "R23")
      (value "10k")
      (footprint "eagle-import:R0402")
      (libsource (lib "eagle-import") (part "R-US_R0402"))
    )
    (comp (ref "R24")
      (value "100k")
      (footprint "eagle-import:R0402")
      (libsource (lib "eagle-import") (part "R-US_R0402"))
    )
    (comp (ref "R25")
      (value "100k")
      (footprint "eagle-import:R0402")
      (libsource (lib "eagle-import") (part "R-US_R0402"))
    )
    (comp (ref "R26")
      (value "100k")
      (footprint "eagle-import:R0402")
      (libsource (lib "eagle-import") (part "R-US_R0402"))
    )
    (comp (ref "R27")
      (value "100k")
      (footprint "eagle-import:R0402")
      (libsource (lib "eagle-import") (part "R-US_R0402"))
    )
    (comp (ref "R28")
      (value "200k")
      (footprint "eagle-import:R0402")
      (libsource (lib "eagle-import") (part "R-US_R0402"))
    )
    (comp (ref "R29")
      (value "200k")
      (footprint "eagle-import:R0402")
      (libsource (lib "eagle-import") (part "R-US_R0402"))
    )
    (comp (ref "R30")
      (value "200k")
      (footprint "eagle-import:R0402")
      (libsource (lib "eagle-import") (part "R-US_R0402"))
    )
    (comp (ref "R31")
      (value "200k")
      (footprint "eagle-import:R0402")
      (libsource (lib "eagle-import") (part "R-US_R0402"))
    )
    (comp (ref "R32")
      (value "100k")
      (footprint "eagle-import:R0402")
      (libsource (lib "eagle-import") (part "R-US_R0402"))
    )
    (comp (ref "R33")
      (value "100k")
      (footprint "eagle-import:R0402")
      (libsource (lib "eagle-import") (part "R-US_R0402"))
    )
    (comp (ref "R34")
      (value "100k")
      (footprint "eagle-import:R0402")
      (libsource (lib "eagle-import") (part "R-US_R0402"))
    )
    (comp (ref "R35")
      (value "100k")
      (footprint "eagle-import:R0402")
      (libsource (lib "eagle-import") (part "R-US_R0402"))
    )
    (comp (ref "R39")
      (value "33k")
      (footprint "eagle-import:R0402")
      (libsource (lib "eagle-import") (part "R-US_R0402"))
    )
    (comp (ref "R40")
      (value "33k")
      (footprint "eagle-import:R0402")
      (libsource (lib "eagle-import") (part "R-US_R0402"))
    )
    (comp (ref "R41")
      (value "33k")
      (footprint "eagle-import:R0402")
      (libsource (lib "eagle-import") (part "R-US_R0402"))
    )
    (comp (ref "R42")
      (value "33k")
      (footprint "eagle-import:R0402")
      (libsource (lib "eagle-import") (part "R-US_R0402"))
    )
    (comp (ref "R57")
      (value "33k")
      (footprint "eagle-import:R0402")
      (libsource (lib "eagle-import") (part "R-US_R0402"))
    )
    (comp (ref "R58")
      (value "33k")
      (footprint "eagle-import:R0402")
      (libsource (lib "eagle-import") (part "R-US_R0402"))
    )
    (comp (ref "R59")
      (value "33k")
      (footprint "eagle-import:R0402")
      (libsource (lib "eagle-import") (part "R-US_R0402"))
    )
    (comp (ref "R64")
      (value "100k")
      (footprint "eagle-import:R0402")
      (libsource (lib "eagle-import") (part "R-US_R0402"))
    )
    (comp (ref "R65")
      (value "100k")
      (footprint "eagle-import:R0402")
      (libsource (lib "eagle-import") (part "R-US_R0402"))
    )
    (comp (ref "R66")
      (value "100k")
      (footprint "eagle-import:R0402")
      (libsource (lib "eagle-import") (part "R-US_R0402"))
    )
    (comp (ref "R70")
      (value "200k")
      (footprint "eagle-import:R0402")
      (libsource (lib "eagle-import") (part "R-US_R0402"))
    )
    (comp (ref "R71")
      (value "200k")
      (footprint "eagle-import:R0402")
      (libsource (lib "eagle-import") (part "R-US_R0402"))
    )
    (comp (ref "R72")
      (value "200k")
      (footprint "eagle-import:R0402")
      (libsource (lib "eagle-import") (part "R-US_R0402"))
    )
    (comp (ref "R76")
      (value "100k")
      (footprint "eagle-import:R0402")
      (libsource (lib "eagle-import") (part "R-US_R0402"))
    )
    (comp (ref "R77")
      (value "100k")
      (footprint "eagle-import:R0402")
      (libsource (lib "eagle-import") (part "R-US_R0402"))
    )
  )
  (nets
    (net (code "1") (name "+3V3") (class "Default")
      (node (ref "C1") (pin "1") (pinfunction "1_1") (pintype "passive"))
      (node (ref "C12") (pin "1") (pinfunction "1_1") (pintype "passive"))
      (node (ref "C13") (pin "1") (pinfunction "1_1") (pintype "passive"))
      (node (ref "C16") (pin "1") (pinfunction "1_1") (pintype "passive"))
      (node (ref "C19") (pin "1") (pinfunction "1_1") (pintype "passive"))
      (node (ref "C2") (pin "+") (pinfunction "+_+") (pintype "passive"))
      (node (ref "C21") (pin "1") (pinfunction "1_1") (pintype "passive"))
      (node (ref "D3") (pin "2") (pinfunction "C_2") (pintype "passive"))
      (node (ref "IC1") (pin "3") (pinfunction "VO_3") (pintype "passive"))
      (node (ref "IC2") (pin "1") (pinfunction "VBAT_1") (pintype "power_in"))
      (node (ref "IC2") (pin "19") (pinfunction "VDD_4_19") (pintype "power_in"))
      (node (ref "IC2") (pin "32") (pinfunction "VDD_1_32") (pintype "power_in"))
      (node (ref "IC2") (pin "48") (pinfunction "VDD_2_48") (pintype "power_in"))
      (node (ref "IC2") (pin "64") (pinfunction "VDD_3_64") (pintype "power_in"))
      (node (ref "IC4") (pin "12") (pinfunction "DVDD_12") (pintype "power_in"))
      (node (ref "R22") (pin "2") (pinfunction "2_2") (pintype "passive"))
      (node (ref "R23") (pin "2") (pinfunction "2_2") (pintype "passive"))
      (node (ref "R6") (pin "2") (pinfunction "2_2") (pintype "passive"))
      (node (ref "U1") (pin "3") (pinfunction "VCC_3") (pintype "power_in"))
    )
    (net (code "2") (name "+3V3_A") (class "Default")
      (node (ref "C10") (pin "1") (pinfunction "1_1") (pintype "passive"))
      (node (ref "C23") (pin "+") (pinfunction "+_+") (pintype "passive"))
      (node (ref "C26") (pin "1") (pinfunction "1_1") (pintype "passive"))
      (node (ref "C27") (pin "+") (pinfunction "+_+") (pintype "passive"))
      (node (ref "C46") (pin "1") (pinfunction "1_1") (pintype "passive"))
      (node (ref "C47") (pin "1") (pinfunction "1_1") (pintype "passive"))
      (node (ref "C9") (pin "1") (pinfunction "1_1") (pintype "passive"))
      (node (ref "IC2") (pin "13") (pinfunction "VDDA_13") (pintype "power_in"))
      (node (ref "IC3") (pin "1") (pinfunction "VO_1") (pintype "passive"))
      (node (ref "IC4") (pin "4") (pinfunction "AVDD_4") (pintype "power_in"))
      (node (ref "IC5") (pin "4") (pinfunction "V+_4") (pintype "power_in"))
      (node (ref "IC6") (pin "4") (pinfunction "V+_4") (pintype "power_in"))
      (node (ref "R13") (pin "P$1") (pinfunction "E_P$1") (pintype "passive"))
      (node (ref "R14") (pin "P$1") (pinfunction "E_P$1") (pintype "passive"))
      (node (ref "R16") (pin "P$1") (pinfunction "E_P$1") (pintype "passive"))
      (node (ref "R20") (pin "P$1") (pinfunction "E_P$1") (pintype "passive"))
      (node (ref "R21") (pin "P$1") (pinfunction "E_P$1") (pintype "passive"))
      (node (ref "R37") (pin "P$1") (pinfunction "E_P$1") (pintype "passive"))
      (node (ref "R38") (pin "P$1") (pinfunction "E_P$1") (pintype "passive"))
      (node (ref "R4") (pin "P$1") (pinfunction "E_P$1") (pintype "passive"))
    )
    (net (code "3") (name "ADC_DV_CV") (class "Default")
      (node (ref "C33") (pin "2") (pinfunction "2_2") (pintype "passive"))
      (node (ref "IC2") (pin "21") (pinfunction "PA5/SPI1_SCK/ADC5/DAC2_21") (pintype "bidirectional"))
      (node (ref "IC6") (pin "8") (pinfunction "OUT_8") (pintype "output"))
      (node (ref "R42") (pin "1") (pinfunction "1_1") (pintype "passive"))
    )
    (net (code "4") (name "ADC_DV_POT") (class "Default")
      (node (ref "C8") (pin "1") (pinfunction "1_1") (pintype "passive"))
      (node (ref "IC2") (pin "11") (pinfunction "PC3/SPI2_MOSI/I2S2_SD/ADC13_11") (pintype "bidirectional"))
      (node (ref "R4") (pin "P$2") (pinfunction "S_P$2") (pintype "passive"))
    )
    (net (code "5") (name "ADC_LENGTH_POT") (class "Default")
      (node (ref "C24") (pin "1") (pinfunction "1_1") (pintype "passive"))
      (node (ref "IC2") (pin "27") (pinfunction "PB1/ADC9/TIM3_CH4_27") (pintype "bidirectional"))
      (node (ref "R16") (pin "P$2") (pinfunction "S_P$2") (pintype "passive"))
    )
    (net (code "6") (name "ADC_T_BIAS_CV") (class "Default")
      (node (ref "C40") (pin "2") (pinfunction "2_2") (pintype "passive"))
      (node (ref "IC2") (pin "15") (pinfunction "PA1/USART2_RTS/UART4_RX/ADC1/TIM2_CH2_15") (pintype "bidirectional"))
      (node (ref "IC5") (pin "1") (pinfunction "OUT_1") (pintype "output"))
      (node (ref "R57") (pin "1") (pinfunction "1_1") (pintype "passive"))
    )
    (net (code "7") (name "ADC_T_BIAS_POT") (class "Default")
      (node (ref "C28") (pin "1") (pinfunction "1_1") (pintype "passive"))
      (node (ref "IC2") (pin "16") (pinfunction "PA2/USART2_TX/ADC2/TIM2_CH3_16") (pintype "bidirectional"))
      (node (ref "R20") (pin "P$2") (pinfunction "S_P$2") (pintype "passive"))
    )
    (net (code "8") (name "ADC_T_JITTER_CV") (class "Default")
      (node (ref "C42") (pin "2") (pinfunction "2_2") (pintype "passive"))
      (node (ref "IC2") (pin "20") (pinfunction "PA4/SPI1_NSS/SPI3_NSS/USART2_CK/I2S3_WS/ADC4/DAC1_20") (pintype "bidirectional"))
      (node (ref "IC6") (pin "7") (pinfunction "OUT_7") (pintype "output"))
      (node (ref "R59") (pin "1") (pinfunction "1_1") (pintype "passive"))
    )
    (net (code "9") (name "ADC_T_JITTER_POT") (class "Default")
      (node (ref "C38") (pin "1") (pinfunction "1_1") (pintype "passive"))
      (node (ref "IC2") (pin "25") (pinfunction "PC5/ADC15_25") (pintype "bidirectional"))
      (node (ref "R37") (pin "P$2") (pinfunction "S_P$2") (pintype "passive"))
    )
    (net (code "10") (name "ADC_T_RATE_CV") (class "Default")
      (node (ref "C41") (pin "2") (pinfunction "2_2") (pintype "passive"))
      (node (ref "IC2") (pin "17") (pinfunction "PA3/USART2_RX/ADC3/TIM2_CH4_17") (pintype "bidirectional"))
      (node (ref "IC6") (pin "1") (pinfunction "OUT_1") (pintype "output"))
      (node (ref "R58") (pin "1") (pinfunction "1_1") (pintype "passive"))
    )
    (net (code "11") (name "ADC_T_RATE_POT") (class "Default")
      (node (ref "C17") (pin "1") (pinfunction "1_1") (pintype "passive"))
      (node (ref "IC2") (pin "10") (pinfunction "PC2/SPI2_MISO/ADC12_10") (pintype "bidirectional"))
      (node (ref "R13") (pin "P$2") (pinfunction "S_P$2") (pintype "passive"))
    )
    (net (code "12") (name "ADC_X_BIAS_CV") (class "Default")
      (node (ref "C30") (pin "2") (pinfunction "2_2") (pintype "passive"))
      (node (ref "IC2") (pin "24") (pinfunction "PC4/ADC14_24") (pintype "bidirectional"))
      (node (ref "IC5") (pin "14") (pinfunction "OUT_14") (pintype "output"))
      (node (ref "R39") (pin "1") (pinfunction "1_1") (pintype "passive"))
    )
    (net (code "13") (name "ADC_X_BIAS_POT") (class "Default")
      (node (ref "C29") (pin "1") (pinfunction "1_1") (pintype "passive"))
      (node (ref "IC2") (pin "9") (pinfunction "PC1/ADC11_9") (pintype "bidirectional"))
      (node (ref "R21") (pin "P$2") (pinfunction "S_P$2") (pintype "passive"))
    )
    (net (code "14") (name "ADC_X_SPREAD_CV") (class "Default")
      (node (ref "C31") (pin "2") (pinfunction "2_2") (pintype "passive"))
      (node (ref "IC2") (pin "14") (pinfunction "PA0-WKUP/USART2_CTS/UART4_TX/ADC0/TIM2_CH1_ETR_14") (pintype "bidirectional"))
      (node (ref "IC2") (pin "23") (pinfunction "PA7/SPI1_MOSI/ADC7/TIM3_CH2_23") (pintype "bidirectional"))
      (node (ref "IC5") (pin "8") (pinfunction "OUT_8") (pintype "output"))
      (node (ref "R40") (pin "1") (pinfunction "1_1") (pintype "passive"))
    )
    (net (code "15") (name "ADC_X_SPREAD_POT") (class "Default")
      (node (ref "C18") (pin "1") (pinfunction "1_1") (pintype "passive"))
      (node (ref "IC2") (pin "8") (pinfunction "PC0/ADC10_8") (pintype "bidirectional"))
      (node (ref "R14") (pin "P$2") (pinfunction "S_P$2") (pintype "passive"))
    )
    (net (code "16") (name "ADC_X_STEPS_CV") (class "Default")
      (node (ref "C32") (pin "2") (pinfunction "2_2") (pintype "passive"))
      (node (ref "IC2") (pin "22") (pinfunction "PA6/SPI1_MISO/ADC6/TIM3_CH1_22") (pintype "bidirectional"))
      (node (ref "IC6") (pin "14") (pinfunction "OUT_14") (pintype "output"))
      (node (ref "R41") (pin "1") (pinfunction "1_1") (pintype "passive"))
    )
    (net (code "17") (name "ADC_X_STEPS_POT") (class "Default")
      (node (ref "C36") (pin "1") (pinfunction "1_1") (pintype "passive"))
      (node (ref "IC2") (pin "26") (pinfunction "PB0/ADC8/TIM3_CH3_26") (pintype "bidirectional"))
      (node (ref "R38") (pin "P$2") (pinfunction "S_P$2") (pintype "passive"))
    )
    (net (code "18") (name "AREF_-10") (class "Default")
      (node (ref "C52") (pin "1") (pinfunction "1_1") (pintype "passive"))
      (node (ref "IC8") (pin "2") (pinfunction "A_2") (pintype "passive"))
      (node (ref "R28") (pin "2") (pinfunction "2_2") (pintype "passive"))
      (node (ref "R29") (pin "2") (pinfunction "2_2") (pintype "passive"))
      (node (ref "R30") (pin "2") (pinfunction "2_2") (pintype "passive"))
      (node (ref "R31") (pin "2") (pinfunction "2_2") (pintype "passive"))
      (node (ref "R68") (pin "2") (pinfunction "2_2") (pintype "passive"))
      (node (ref "R70") (pin "2") (pinfunction "2_2") (pintype "passive"))
      (node (ref "R71") (pin "2") (pinfunction "2_2") (pintype "passive"))
      (node (ref "R72") (pin "2") (pinfunction "2_2") (pintype "passive"))
    )
    (net (code "19") (name "DAC_MOSI") (class "Default")
      (node (ref "IC2") (pin "53") (pinfunction "PC12/UART5_TX/I2S3_SD/USART3_CK_53") (pintype "bidirectional"))
      (node (ref "IC4") (pin "11") (pinfunction "IN_11") (pintype "input"))
    )
    (net (code "20") (name "DAC_SCK") (class "Default")
      (node (ref "IC2") (pin "51") (pinfunction "PC10/SPI3_SCK/I2S3_SCK/UART4_TX_51") (pintype "bidirectional"))
      (node (ref "IC4") (pin "10") (pinfunction "SCK_10") (pintype "input"))
    )
    (net (code "21") (name "DAC_SS") (class "Default")
      (node (ref "IC2") (pin "50") (pinfunction "PA15/JTDI/SPI3_NSS/I2S3_WS_50") (pintype "bidirectional"))
      (node (ref "IC4") (pin "9") (pinfunction "SYNC_9") (pintype "input"))
    )
    (net (code "22") (name "DAC_X_1") (class "Default")
      (node (ref "IC4") (pin "2") (pinfunction "OUTB_2") (pintype "output"))
      (node (ref "R47") (pin "2") (pinfunction "2_2") (pintype "passive"))
    )
    (net (code "23") (name "DAC_X_2") (class "Default")
      (node (ref "IC4") (pin "7") (pinfunction "OUTC_7") (pintype "output"))
      (node (ref "R48") (pin "2") (pinfunction "2_2") (pintype "passive"))
    )
    (net (code "24") (name "DAC_X_3") (class "Default")
      (node (ref "IC4") (pin "8") (pinfunction "OUTD_8") (pintype "output"))
      (node (ref "R53") (pin "2") (pinfunction "2_2") (pintype "passive"))
    )
    (net (code "25") (name "DAC_Y") (class "Default")
      (node (ref "IC4") (pin "1") (pinfunction "OUTA_1") (pintype "output"))
      (node (ref "R54") (pin "2") (pinfunction "2_2") (pintype "passive"))
    )
    (net (code "26") (name "DEPRECATED") (class "Default")
      (node (ref "IC5") (pin "6") (pinfunction "-IN_6") (pintype "input"))
      (node (ref "IC5") (pin "7") (pinfunction "OUT_7") (pintype "output"))
    )
    (net (code "27") (name "GATE_T_1") (class "Default")
      (node (ref "IC2") (pin "52") (pinfunction "PC11/UART4_RX/SPI3_MISO/USART3_RX_52") (pintype "bidirectional"))
      (node (ref "LED6") (pin "1") (pinfunction "1_1") (pintype "bidirectional"))
      (node (ref "R56") (pin "2") (pinfunction "2_2") (pintype "passive"))
    )
    (net (code "28") (name "GATE_T_2") (class "Default")
      (node (ref "IC2") (pin "44") (pinfunction "PA11/USART1_CTS/CANRX/USBDM/TIM1_CH4_44") (pintype "bidirectional"))
      (node (ref "LED7") (pin "1") (pinfunction "1_1") (pintype "bidirectional"))
      (node (ref "R55") (pin "2") (pinfunction "2_2") (pintype "passive"))
    )
    (net (code "29") (name "GATE_T_3") (class "Default")
      (node (ref "IC2") (pin "45") (pinfunction "PA12/USART1_RTS/CANTX/USBDP/TIM1_ETR_45") (pintype "bidirectional"))
      (node (ref "LED8") (pin "1") (pinfunction "1_1") (pintype "bidirectional"))
      (node (ref "R67") (pin "2") (pinfunction "2_2") (pintype "passive"))
    )
    (net (code "30") (name "GND") (class "Default")
      (node (ref "C1") (pin "2") (pinfunction "2_2") (pintype "passive"))
      (node (ref "C10") (pin "2") (pinfunction "2_2") (pintype "passive"))
      (node (ref "C11") (pin "-") (pinfunction "-_-") (pintype "passive"))
      (node (ref "C12") (pin "2") (pinfunction "2_2") (pintype "passive"))
      (node (ref "C13") (pin "2") (pinfunction "2_2") (pintype "passive"))
      (node (ref "C14") (pin "2") (pinfunction "2_2") (pintype "passive"))
      (node (ref "C15") (pin "2") (pinfunction "2_2") (pintype "passive"))
      (node (ref "C16") (pin "2") (pinfunction "2_2") (pintype "passive"))
      (node (ref "C17") (pin "2") (pinfunction "2_2") (pintype "passive"))
      (node (ref "C18") (pin "2") (pinfunction "2_2") (pintype "passive"))
      (node (ref "C19") (pin "2") (pinfunction "2_2") (pintype "passive"))
      (node (ref "C2") (pin "-") (pinfunction "-_-") (pintype "passive"))
      (node (ref "C20") (pin "2") (pinfunction "2_2") (pintype "passive"))
      (node (ref "C21") (pin "2") (pinfunction "2_2") (pintype "passive"))
      (node (ref "C22") (pin "+") (pinfunction "+_+") (pintype "passive"))
      (node (ref "C23") (pin "-") (pinfunction "-_-") (pintype "passive"))
      (node (ref "C24") (pin "2") (pinfunction "2_2") (pintype "passive"))
      (node (ref "C25") (pin "2") (pinfunction "2_2") (pintype "passive"))
      (node (ref "C26") (pin "2") (pinfunction "2_2") (pintype "passive"))
      (node (ref "C27") (pin "-") (pinfunction "-_-") (pintype "passive"))
      (node (ref "C28") (pin "2") (pinfunction "2_2") (pintype "passive"))
      (node (ref "C29") (pin "2") (pinfunction "2_2") (pintype "passive"))
      (node (ref "C3") (pin "2") (pinfunction "2_2") (pintype "passive"))
      (node (ref "C36") (pin "2") (pinfunction "2_2") (pintype "passive"))
      (node (ref "C37") (pin "1") (pinfunction "1_1") (pintype "passive"))
      (node (ref "C38") (pin "2") (pinfunction "2_2") (pintype "passive"))
      (node (ref "C39") (pin "2") (pinfunction "2_2") (pintype "passive"))
      (node (ref "C4") (pin "1") (pinfunction "1_1") (pintype "passive"))
      (node (ref "C45") (pin "2") (pinfunction "2_2") (pintype "passive"))
      (node (ref "C46") (pin "2") (pinfunction "2_2") (pintype "passive"))
      (node (ref "C47") (pin "2") (pinfunction "2_2") (pintype "passive"))
      (node (ref "C48") (pin "2") (pinfunction "2_2") (pintype "passive"))
      (node (ref "C49") (pin "1") (pinfunction "1_1") (pintype "passive"))
      (node (ref "C5") (pin "2") (pinfunction "2_2") (pintype "passive"))
      (node (ref "C50") (pin "2") (pinfunction "2_2") (pintype "passive"))
      (node (ref "C51") (pin "2") (pinfunction "2_2") (pintype "passive"))
      (node (ref "C52") (pin "2") (pinfunction "2_2") (pintype "passive"))
      (node (ref "C53") (pin "2") (pinfunction "2_2") (pintype "passive"))
      (node (ref "C54") (pin "2") (pinfunction "2_2") (pintype "passive"))
      (node (ref "C55") (pin "2") (pinfunction "2_2") (pintype "passive"))
      (node (ref "C56") (pin "2") (pinfunction "2_2") (pintype "passive"))
      (node (ref "C57") (pin "2") (pinfunction "2_2") (pintype "passive"))
      (node (ref "C58") (pin "2") (pinfunction "2_2") (pintype "passive"))
      (node (ref "C6") (pin "1") (pinfunction "1_1") (pintype "passive"))
      (node (ref "C7") (pin "2") (pinfunction "2_2") (pintype "passive"))
      (node (ref "C8") (pin "2") (pinfunction "2_2") (pintype "passive"))
      (node (ref "C9") (pin "2") (pinfunction "2_2") (pintype "passive"))
      (node (ref "D3") (pin "1") (pinfunction "A_1") (pintype "passive"))
      (node (ref "D4") (pin "A") (pinfunction "A_A") (pintype "passive"))
      (node (ref "D5") (pin "A") (pinfunction "A_A") (pintype "passive"))
      (node (ref "IC1") (pin "2") (pinfunction "GND_2") (pintype "passive"))
      (node (ref "IC2") (pin "12") (pinfunction "VSSA_12") (pintype "power_in"))
      (node (ref "IC2") (pin "18") (pinfunction "VSS_4_18") (pintype "power_in"))
      (node (ref "IC2") (pin "28") (pinfunction "PB2/BOOT1_28") (pintype "bidirectional"))
      (node (ref "IC2") (pin "60") (pinfunction "BOOT0_60") (pintype "bidirectional"))
      (node (ref "IC2") (pin "63") (pinfunction "VSS_3_63") (pintype "power_in"))
      (node (ref "IC3") (pin "2") (pinfunction "GND_2") (pintype "passive"))
      (node (ref "IC4") (pin "13") (pinfunction "A0_13") (pintype "input"))
      (node (ref "IC4") (pin "14") (pinfunction "A1_14") (pintype "input"))
      (node (ref "IC4") (pin "15") (pinfunction "ENABLE_15") (pintype "input"))
      (node (ref "IC4") (pin "16") (pinfunction "LDAC_16") (pintype "input"))
      (node (ref "IC4") (pin "5") (pinfunction "VREFL_5") (pintype "bidirectional"))
      (node (ref "IC4") (pin "6") (pinfunction "GND_6") (pintype "power_in"))
      (node (ref "IC5") (pin "10") (pinfunction "+IN_10") (pintype "input"))
      (node (ref "IC5") (pin "11") (pinfunction "V-_11") (pintype "power_in"))
      (node (ref "IC5") (pin "12") (pinfunction "+IN_12") (pintype "input"))
      (node (ref "IC5") (pin "3") (pinfunction "+IN_3") (pintype "input"))
      (node (ref "IC5") (pin "5") (pinfunction "+IN_5") (pintype "input"))
      (node (ref "IC6") (pin "10") (pinfunction "+IN_10") (pintype "input"))
      (node (ref "IC6") (pin "11") (pinfunction "V-_11") (pintype "power_in"))
      (node (ref "IC6") (pin "12") (pinfunction "+IN_12") (pintype "input"))
      (node (ref "IC6") (pin "3") (pinfunction "+IN_3") (pintype "input"))
      (node (ref "IC6") (pin "5") (pinfunction "+IN_5") (pintype "input"))
      (node (ref "IC8") (pin "1") (pinfunction "C_1") (pintype "passive"))
      (node (ref "IC9") (pin "11") (pinfunction "V-_11") (pintype "power_in"))
      (node (ref "IC9") (pin "5") (pinfunction "+IN_5") (pintype "input"))
      (node (ref "J1") (pin "P1") (pinfunction "1_P1") (pintype "passive"))
      (node (ref "J1") (pin "P2") (pinfunction "2_P2") (pintype "passive"))
      (node (ref "J10") (pin "P1") (pinfunction "1_P1") (pintype "passive"))
      (node (ref "J11") (pin "P1") (pinfunction "1_P1") (pintype "passive"))
      (node (ref "J12") (pin "P1") (pinfunction "1_P1") (pintype "passive"))
      (node (ref "J13") (pin "P1") (pinfunction "1_P1") (pintype "passive"))
      (node (ref "J14") (pin "P1") (pinfunction "1_P1") (pintype "passive"))
      (node (ref "J15") (pin "P1") (pinfunction "1_P1") (pintype "passive"))
      (node (ref "J16") (pin "P1") (pinfunction "1_P1") (pintype "passive"))
      (node (ref "J2") (pin "P1") (pinfunction "1_P1") (pintype "passive"))
      (node (ref "J2") (pin "P2") (pinfunction "2_P2") (pintype "passive"))
      (node (ref "J3") (pin "P1") (pinfunction "1_P1") (pintype "passive"))
      (node (ref "J4") (pin "P1") (pinfunction "1_P1") (pintype "passive"))
      (node (ref "J4") (pin "P2") (pinfunction "2_P2") (pintype "passive"))
      (node (ref "J5") (pin "P1") (pinfunction "1_P1") (pintype "passive"))
      (node (ref "J5") (pin "P2") (pinfunction "2_P2") (pintype "passive"))
      (node (ref "J6") (pin "P1") (pinfunction "1_P1") (pintype "passive"))
      (node (ref "J6") (pin "P2") (pinfunction "2_P2") (pintype "passive"))
      (node (ref "J7") (pin "P1") (pinfunction "1_P1") (pintype "passive"))
      (node (ref "J7") (pin "P2") (pinfunction "2_P2") (pintype "passive"))
      (node (ref "J8") (pin "P1") (pinfunction "1_P1") (pintype "passive"))
      (node (ref "J8") (pin "P2") (pinfunction "2_P2") (pintype "passive"))
      (node (ref "J9") (pin "P1") (pinfunction "1_P1") (pintype "passive"))
      (node (ref "JP1") (pin "1") (pinfunction "1_1") (pintype "passive"))
      (node (ref "JP4") (pin "3") (pinfunction "3_3") (pintype "passive"))
      (node (ref "JP4") (pin "4") (pinfunction "4_4") (pintype "passive"))
      (node (ref "JP4") (pin "5") (pinfunction "5_5") (pintype "passive"))
      (node (ref "JP4") (pin "6") (pinfunction "6_6") (pintype "passive"))
      (node (ref "JP4") (pin "7") (pinfunction "7_7") (pintype "passive"))
      (node (ref "JP4") (pin "8") (pinfunction "8_8") (pintype "passive"))
      (node (ref "LED1") (pin "2") (pinfunction "C_2") (pintype "bidirectional"))
      (node (ref "LED2") (pin "2") (pinfunction "C_2") (pintype "bidirectional"))
      (node (ref "LED3") (pin "2") (pinfunction "C_2") (pintype "bidirectional"))
      (node (ref "LED4") (pin "2") (pinfunction "C_2") (pintype "bidirectional"))
      (node (ref "LED5") (pin "2") (pinfunction "C_2") (pintype "bidirectional"))
      (node (ref "Q1") (pin "2") (pinfunction "LID1_2") (pintype "power_in"))
      (node (ref "Q1") (pin "4") (pinfunction "LID2_4") (pintype "power_in"))
      (node (ref "Q2") (pin "E") (pinfunction "E_E") (pintype "passive"))
      (node (ref "Q3") (pin "E") (pinfunction "E_E") (pintype "passive"))
      (node (ref "R13") (pin "P$3") (pinfunction "A_P$3") (pintype "passive"))
      (node (ref "R14") (pin "P$3") (pinfunction "A_P$3") (pintype "passive"))
      (node (ref "R16") (pin "P$3") (pinfunction "A_P$3") (pintype "passive"))
      (node (ref "R20") (pin "P$3") (pinfunction "A_P$3") (pintype "passive"))
      (node (ref "R21") (pin "P$3") (pinfunction "A_P$3") (pintype "passive"))
      (node (ref "R24") (pin "1") (pinfunction "1_1") (pintype "passive"))
      (node (ref "R25") (pin "1") (pinfunction "1_1") (pintype "passive"))
      (node (ref "R37") (pin "P$3") (pinfunction "A_P$3") (pintype "passive"))
      (node (ref "R38") (pin "P$3") (pinfunction "A_P$3") (pintype "passive"))
      (node (ref "R4") (pin "P$3") (pinfunction "A_P$3") (pintype "passive"))
      (node (ref "R49") (pin "2") (pinfunction "2_2") (pintype "passive"))
      (node (ref "R50") (pin "2") (pinfunction "2_2") (pintype "passive"))
      (node (ref "R73") (pin "1") (pinfunction "1_1") (pintype "passive"))
      (node (ref "R75") (pin "2") (pinfunction "2_2") (pintype "passive"))
      (node (ref "R78") (pin "2") (pinfunction "2_2") (pintype "passive"))
      (node (ref "R79") (pin "2") (pinfunction "2_2") (pintype "passive"))
      (node (ref "R80") (pin "2") (pinfunction "2_2") (pintype "passive"))
      (node (ref "R81") (pin "2") (pinfunction "2_2") (pintype "passive"))
      (node (ref "R82") (pin "1") (pinfunction "1_1") (pintype "passive"))
      (node (ref "R83") (pin "1") (pinfunction "1_1") (pintype "passive"))
      (node (ref "R84") (pin "1") (pinfunction "1_1") (pintype "passive"))
      (node (ref "SW1") (pin "L2") (pinfunction "L2_L2") (pintype "passive"))
      (node (ref "SW1") (pin "P3") (pinfunction "A3_P3") (pintype "passive"))
      (node (ref "SW1") (pin "P6") (pinfunction "B3_P6") (pintype "passive"))
      (node (ref "SW2") (pin "L2") (pinfunction "L2_L2") (pintype "passive"))
      (node (ref "SW2") (pin "P3") (pinfunction "A3_P3") (pintype "passive"))
      (node (ref "SW2") (pin "P6") (pinfunction "B3_P6") (pintype "passive"))
      (node (ref "SW3") (pin "1") (pinfunction "1_1") (pintype "passive"))
      (node (ref "SW3") (pin "2") (pinfunction "2_2") (pintype "passive"))
      (node (ref "SW4") (pin "1") (pinfunction "1_1") (pintype "passive"))
      (node (ref "SW4") (pin "2") (pinfunction "2_2") (pintype "passive"))
      (node (ref "SW5") (pin "1") (pinfunction "1_1") (pintype "passive"))
      (node (ref "SW5") (pin "2") (pinfunction "2_2") (pintype "passive"))
      (node (ref "SW6") (pin "1") (pinfunction "1_1") (pintype "passive"))
      (node (ref "SW6") (pin "2") (pinfunction "2_2") (pintype "passive"))
      (node (ref "SW7") (pin "1") (pinfunction "1_1") (pintype "passive"))
      (node (ref "SW7") (pin "2") (pinfunction "2_2") (pintype "passive"))
      (node (ref "U1") (pin "1") (pinfunction "GND_1") (pintype "passive"))
    )
    (net (code "31") (name "LED_T_DV") (class "Default")
      (node (ref "IC2") (pin "29") (pinfunction "PB10/SPI2_SCK/I2S_SCK/I2C2_SCL/USART3_TX_29") (pintype "bidirectional"))
      (node (ref "R1") (pin "1") (pinfunction "1_1") (pintype "passive"))
    )
    (net (code "32") (name "LED_T_MODE_G") (class "Default")
      (node (ref "IC2") (pin "33") (pinfunction "PB12/SPI2_NSS/I2S2_WS/I2C2_SMBA/USART3_CK/TIM1_BKIN_33") (pintype "bidirectional"))
      (node (ref "R10") (pin "1") (pinfunction "1_1") (pintype "passive"))
    )
    (net (code "33") (name "LED_T_MODE_R") (class "Default")
      (node (ref "IC2") (pin "34") (pinfunction "PB13/SPI2_SCK/I2S2_SCK/USART3_CTS/TIM1_CH1N_34") (pintype "bidirectional"))
      (node (ref "R9") (pin "1") (pinfunction "1_1") (pintype "passive"))
    )
    (net (code "34") (name "LED_T_RANGE_G") (class "Default")
      (node (ref "IC2") (pin "37") (pinfunction "PC6/I2S2_MCK_37") (pintype "bidirectional"))
      (node (ref "R18") (pin "1") (pinfunction "1_1") (pintype "passive"))
    )
    (net (code "35") (name "LED_T_RANGE_R") (class "Default")
      (node (ref "IC2") (pin "38") (pinfunction "PC7/I2S3_MCK_38") (pintype "bidirectional"))
      (node (ref "R19") (pin "1") (pinfunction "1_1") (pintype "passive"))
    )
    (net (code "36") (name "LED_X_DV") (class "Default")
      (node (ref "IC2") (pin "62") (pinfunction "PB9/SPI2_NSS/I2S2_WS/I2C1_SDA/TIM4_CH4_62") (pintype "bidirectional"))
      (node (ref "R5") (pin "1") (pinfunction "1_1") (pintype "passive"))
    )
    (net (code "37") (name "LED_X_EXT_G") (class "Default")
      (node (ref "IC2") (pin "55") (pinfunction "PB3/JTDO/SPI3_SCK/I2S3_SCK_55") (pintype "bidirectional"))
      (node (ref "R36") (pin "1") (pinfunction "1_1") (pintype "passive"))
    )
    (net (code "38") (name "LED_X_MODE_G") (class "Default")
      (node (ref "IC2") (pin "59") (pinfunction "PB7/I2C1_SDA/TIM4_CH2/USART1_RX_59") (pintype "bidirectional"))
      (node (ref "R12") (pin "1") (pinfunction "1_1") (pintype "passive"))
    )
    (net (code "39") (name "LED_X_MODE_R") (class "Default")
      (node (ref "IC2") (pin "61") (pinfunction "PB8/TIM4_CH3/I2C1_SCL_61") (pintype "bidirectional"))
      (node (ref "R11") (pin "1") (pinfunction "1_1") (pintype "passive"))
    )
    (net (code "40") (name "LED_X_RANGE_G") (class "Default")
      (node (ref "IC2") (pin "57") (pinfunction "PB5/I2C1_SMBA/SPI1_MOSI/SPI3_MOSI/I2S3_SD_57") (pintype "bidirectional"))
      (node (ref "R17") (pin "1") (pinfunction "1_1") (pintype "passive"))
    )
    (net (code "41") (name "LED_X_RANGE_R") (class "Default")
      (node (ref "IC2") (pin "56") (pinfunction "PB4/NJTRST/SPI3_MISO/SPI1_MISO_56") (pintype "bidirectional"))
      (node (ref "R15") (pin "1") (pinfunction "1_1") (pintype "passive"))
    )
    (net (code "42") (name "NORMALIZATION_PROBE") (class "Default")
      (node (ref "D3") (pin "3") (pinfunction "AC_3") (pintype "passive"))
      (node (ref "IC2") (pin "39") (pinfunction "PC8_39") (pintype "bidirectional"))
      (node (ref "R76") (pin "1") (pinfunction "1_1") (pintype "passive"))
      (node (ref "R77") (pin "1") (pinfunction "1_1") (pintype "passive"))
    )
    (net (code "43") (name "Net-(C5-Pad1)") (class "Default")
      (node (ref "C5") (pin "1") (pinfunction "1_1") (pintype "passive"))
      (node (ref "D1") (pin "C") (pinfunction "C_C") (pintype "passive"))
      (node (ref "L1") (pin "1") (pinfunction "1_1") (pintype "passive"))
      (node (ref "L2") (pin "2") (pinfunction "2_2") (pintype "passive"))
      (node (ref "L3") (pin "2") (pinfunction "2_2") (pintype "passive"))
    )
    (net (code "44") (name "Net-(C6-Pad2)") (class "Default")
      (node (ref "C6") (pin "2") (pinfunction "2_2") (pintype "passive"))
      (node (ref "Q1") (pin "1") (pinfunction "1_1") (pintype "passive"))
      (node (ref "R7") (pin "2") (pinfunction "2_2") (pintype "passive"))
    )
    (net (code "45") (name "Net-(D1-PadA)") (class "Default")
      (node (ref "D1") (pin "A") (pinfunction "A_A") (pintype "passive"))
      (node (ref "JP4") (pin "10") (pinfunction "10_10") (pintype "passive"))
      (node (ref "JP4") (pin "9") (pinfunction "9_9") (pintype "passive"))
    )
    (net (code "46") (name "Net-(D2-PadA)") (class "Default")
      (node (ref "D2") (pin "A") (pinfunction "A_A") (pintype "passive"))
      (node (ref "L4") (pin "2") (pinfunction "2_2") (pintype "passive"))
    )
    (net (code "47") (name "Net-(D2-PadC)") (class "Default")
      (node (ref "D2") (pin "C") (pinfunction "C_C") (pintype "passive"))
      (node (ref "JP4") (pin "1") (pinfunction "1_1") (pintype "passive"))
      (node (ref "JP4") (pin "2") (pinfunction "2_2") (pintype "passive"))
    )
    (net (code "48") (name "Net-(D4-PadC)") (class "Default")
      (node (ref "D4") (pin "C") (pinfunction "C_C") (pintype "passive"))
      (node (ref "Q2") (pin "B") (pinfunction "B_B") (pintype "passive"))
      (node (ref "R24") (pin "2") (pinfunction "2_2") (pintype "passive"))
      (node (ref "R26") (pin "2") (pinfunction "2_2") (pintype "passive"))
    )
    (net (code "49") (name "Net-(D5-PadC)") (class "Default")
      (node (ref "D5") (pin "C") (pinfunction "C_C") (pintype "passive"))
      (node (ref "Q3") (pin "B") (pinfunction "B_B") (pintype "passive"))
      (node (ref "R25") (pin "2") (pinfunction "2_2") (pintype "passive"))
      (node (ref "R27") (pin "2") (pinfunction "2_2") (pintype "passive"))
    )
    (net (code "50") (name "Net-(IC1-VI)") (class "Default")
      (node (ref "C3") (pin "1") (pinfunction "1_1") (pintype "passive"))
      (node (ref "IC1") (pin "1") (pinfunction "VI_1") (pintype "input"))
      (node (ref "L1") (pin "2") (pinfunction "2_2") (pintype "passive"))
    )
    (net (code "51") (name "Net-(IC2-PD0{slash}OSC_IN)") (class "Default")
      (node (ref "IC2") (pin "5") (pinfunction "PD0/OSC_IN_5") (pintype "bidirectional"))
      (node (ref "R8") (pin "1") (pinfunction "1_1") (pintype "passive"))
    )
    (net (code "52") (name "Net-(IC2-PD1{slash}OSC_OUT)") (class "Default")
      (node (ref "IC2") (pin "6") (pinfunction "PD1/OSC_OUT_6") (pintype "bidirectional"))
      (node (ref "R7") (pin "1") (pinfunction "1_1") (pintype "passive"))
    )
    (net (code "53") (name "Net-(IC2-VCAP_1)") (class "Default")
      (node (ref "C15") (pin "1") (pinfunction "1_1") (pintype "passive"))
      (node (ref "IC2") (pin "31") (pinfunction "VCAP_1_31") (pintype "power_in"))
    )
    (net (code "54") (name "Net-(IC2-VCAP_2)") (class "Default")
      (node (ref "C20") (pin "1") (pinfunction "1_1") (pintype "passive"))
      (node (ref "IC2") (pin "47") (pinfunction "VCAP_2_47") (pintype "power_in"))
    )
    (net (code "55") (name "Net-(IC3-VI)") (class "Default")
      (node (ref "C14") (pin "1") (pinfunction "1_1") (pintype "passive"))
      (node (ref "IC3") (pin "3") (pinfunction "VI_3") (pintype "input"))
      (node (ref "L3") (pin "1") (pinfunction "1_1") (pintype "passive"))
    )
    (net (code "56") (name "Net-(IC5A--IN)") (class "Default")
      (node (ref "C40") (pin "1") (pinfunction "1_1") (pintype "passive"))
      (node (ref "IC5") (pin "2") (pinfunction "-IN_2") (pintype "input"))
      (node (ref "R57") (pin "2") (pinfunction "2_2") (pintype "passive"))
      (node (ref "R64") (pin "1") (pinfunction "1_1") (pintype "passive"))
      (node (ref "R70") (pin "1") (pinfunction "1_1") (pintype "passive"))
    )
    (net (code "57") (name "Net-(IC5C--IN)") (class "Default")
      (node (ref "C31") (pin "1") (pinfunction "1_1") (pintype "passive"))
      (node (ref "IC5") (pin "9") (pinfunction "-IN_9") (pintype "input"))
      (node (ref "R28") (pin "1") (pinfunction "1_1") (pintype "passive"))
      (node (ref "R34") (pin "1") (pinfunction "1_1") (pintype "passive"))
      (node (ref "R40") (pin "2") (pinfunction "2_2") (pintype "passive"))
    )
    (net (code "58") (name "Net-(IC5D--IN)") (class "Default")
      (node (ref "C30") (pin "1") (pinfunction "1_1") (pintype "passive"))
      (node (ref "IC5") (pin "13") (pinfunction "-IN_13") (pintype "input"))
      (node (ref "R30") (pin "1") (pinfunction "1_1") (pintype "passive"))
      (node (ref "R33") (pin "1") (pinfunction "1_1") (pintype "passive"))
      (node (ref "R39") (pin "2") (pinfunction "2_2") (pintype "passive"))
    )
    (net (code "59") (name "Net-(IC6A--IN)") (class "Default")
      (node (ref "C41") (pin "1") (pinfunction "1_1") (pintype "passive"))
      (node (ref "IC6") (pin "2") (pinfunction "-IN_2") (pintype "input"))
      (node (ref "R58") (pin "2") (pinfunction "2_2") (pintype "passive"))
      (node (ref "R65") (pin "1") (pinfunction "1_1") (pintype "passive"))
      (node (ref "R71") (pin "1") (pinfunction "1_1") (pintype "passive"))
    )
    (net (code "60") (name "Net-(IC6B--IN)") (class "Default")
      (node (ref "C42") (pin "1") (pinfunction "1_1") (pintype "passive"))
      (node (ref "IC6") (pin "6") (pinfunction "-IN_6") (pintype "input"))
      (node (ref "R59") (pin "2") (pinfunction "2_2") (pintype "passive"))
      (node (ref "R66") (pin "1") (pinfunction "1_1") (pintype "passive"))
      (node (ref "R72") (pin "1") (pinfunction "1_1") (pintype "passive"))
    )
    (net (code "61") (name "Net-(IC6C--IN)") (class "Default")
      (node (ref "C33") (pin "1") (pinfunction "1_1") (pintype "passive"))
      (node (ref "IC6") (pin "9") (pinfunction "-IN_9") (pintype "input"))
      (node (ref "R31") (pin "1") (pinfunction "1_1") (pintype "passive"))
      (node (ref "R32") (pin "1") (pinfunction "1_1") (pintype "passive"))
      (node (ref "R42") (pin "2") (pinfunction "2_2") (pintype "passive"))
    )
    (net (code "62") (name "Net-(IC6D--IN)") (class "Default")
      (node (ref "C32") (pin "1") (pinfunction "1_1") (pintype "passive"))
      (node (ref "IC6") (pin "13") (pinfunction "-IN_13") (pintype "input"))
      (node (ref "R29") (pin "1") (pinfunction "1_1") (pintype "passive"))
      (node (ref "R35") (pin "1") (pinfunction "1_1") (pintype "passive"))
      (node (ref "R41") (pin "2") (pinfunction "2_2") (pintype "passive"))
    )
    (net (code "63") (name "Net-(IC7A--IN)") (class "Default")
      (node (ref "C34") (pin "1") (pinfunction "1_1") (pintype "passive"))
      (node (ref "IC7") (pin "2") (pinfunction "-IN_2") (pintype "input"))
      (node (ref "R43") (pin "2") (pinfunction "2_2") (pintype "passive"))
      (node (ref "R47") (pin "1") (pinfunction "1_1") (pintype "passive"))
    )
    (net (code "64") (name "Net-(IC7B--IN)") (class "Default")
      (node (ref "C43") (pin "1") (pinfunction "1_1") (pintype "passive"))
      (node (ref "IC7") (pin "6") (pinfunction "-IN_6") (pintype "input"))
      (node (ref "R54") (pin "1") (pinfunction "1_1") (pintype "passive"))
      (node (ref "R60") (pin "2") (pinfunction "2_2") (pintype "passive"))
    )
    (net (code "65") (name "Net-(IC7C--IN)") (class "Default")
      (node (ref "C44") (pin "1") (pinfunction "1_1") (pintype "passive"))
      (node (ref "IC7") (pin "9") (pinfunction "-IN_9") (pintype "input"))
      (node (ref "R53") (pin "1") (pinfunction "1_1") (pintype "passive"))
      (node (ref "R61") (pin "2") (pinfunction "2_2") (pintype "passive"))
    )
    (net (code "66") (name "Net-(IC7D--IN)") (class "Default")
      (node (ref "C35") (pin "1") (pinfunction "1_1") (pintype "passive"))
      (node (ref "IC7") (pin "13") (pinfunction "-IN_13") (pintype "input"))
      (node (ref "R44") (pin "2") (pinfunction "2_2") (pintype "passive"))
      (node (ref "R48") (pin "1") (pinfunction "1_1") (pintype "passive"))
    )
    (net (code "67") (name "Net-(IC9A-+IN)") (class "Default")
      (node (ref "IC9") (pin "3") (pinfunction "+IN_3") (pintype "input"))
      (node (ref "R56") (pin "1") (pinfunction "1_1") (pintype "passive"))
    )
    (net (code "68") (name "Net-(IC9A--IN)") (class "Default")
      (node (ref "IC9") (pin "2") (pinfunction "-IN_2") (pintype "input"))
      (node (ref "R50") (pin "1") (pinfunction "1_1") (pintype "passive"))
      (node (ref "R51") (pin "2") (pinfunction "2_2") (pintype "passive"))
    )
    (net (code "69") (name "Net-(IC9A-OUT)") (class "Default")
      (node (ref "IC9") (pin "1") (pinfunction "OUT_1") (pintype "output"))
      (node (ref "R51") (pin "1") (pinfunction "1_1") (pintype "passive"))
      (node (ref "R85") (pin "2") (pinfunction "2_2") (pintype "passive"))
    )
    (net (code "70") (name "Net-(IC9B--IN)") (class "Default")
      (node (ref "IC9") (pin "6") (pinfunction "-IN_6") (pintype "input"))
      (node (ref "IC9") (pin "7") (pinfunction "OUT_7") (pintype "output"))
    )
    (net (code "71") (name "Net-(IC9C-+IN)") (class "Default")
      (node (ref "IC9") (pin "10") (pinfunction "+IN_10") (pintype "input"))
      (node (ref "R67") (pin "1") (pinfunction "1_1") (pintype "passive"))
    )
    (net (code "72") (name "Net-(IC9C--IN)") (class "Default")
      (node (ref "IC9") (pin "9") (pinfunction "-IN_9") (pintype "input"))
      (node (ref "R69") (pin "2") (pinfunction "2_2") (pintype "passive"))
      (node (ref "R75") (pin "1") (pinfunction "1_1") (pintype "passive"))
    )
    (net (code "73") (name "Net-(IC9C-OUT)") (class "Default")
      (node (ref "IC9") (pin "8") (pinfunction "OUT_8") (pintype "output"))
      (node (ref "R69") (pin "1") (pinfunction "1_1") (pintype "passive"))
      (node (ref "R87") (pin "2") (pinfunction "2_2") (pintype "passive"))
    )
    (net (code "74") (name "Net-(IC9D-+IN)") (class "Default")
      (node (ref "IC9") (pin "12") (pinfunction "+IN_12") (pintype "input"))
      (node (ref "R55") (pin "1") (pinfunction "1_1") (pintype "passive"))
    )
    (net (code "75") (name "Net-(IC9D--IN)") (class "Default")
      (node (ref "IC9") (pin "13") (pinfunction "-IN_13") (pintype "input"))
      (node (ref "R49") (pin "1") (pinfunction "1_1") (pintype "passive"))
      (node (ref "R52") (pin "2") (pinfunction "2_2") (pintype "passive"))
    )
    (net (code "76") (name "Net-(IC9D-OUT)") (class "Default")
      (node (ref "IC9") (pin "14") (pinfunction "OUT_14") (pintype "output"))
      (node (ref "R52") (pin "1") (pinfunction "1_1") (pintype "passive"))
      (node (ref "R86") (pin "2") (pinfunction "2_2") (pintype "passive"))
    )
    (net (code "77") (name "Net-(IC10A-+IN)") (class "Default")
      (node (ref "C34") (pin "2") (pinfunction "2_2") (pintype "passive"))
      (node (ref "IC10") (pin "3") (pinfunction "+IN_3") (pintype "input"))
      (node (ref "IC7") (pin "1") (pinfunction "OUT_1") (pintype "output"))
      (node (ref "R45") (pin "2") (pinfunction "2_2") (pintype "passive"))
    )
    (net (code "78") (name "Net-(IC10A--IN)") (class "Default")
      (node (ref "IC10") (pin "2") (pinfunction "-IN_2") (pintype "input"))
      (node (ref "LED10") (pin "2") (pinfunction "2_2") (pintype "bidirectional"))
      (node (ref "R79") (pin "1") (pinfunction "1_1") (pintype "passive"))
    )
    (net (code "79") (name "Net-(IC10A-OUT)") (class "Default")
      (node (ref "IC10") (pin "1") (pinfunction "OUT_1") (pintype "output"))
      (node (ref "LED10") (pin "1") (pinfunction "1_1") (pintype "bidirectional"))
    )
    (net (code "80") (name "Net-(IC10B-+IN)") (class "Default")
      (node (ref "C43") (pin "2") (pinfunction "2_2") (pintype "passive"))
      (node (ref "IC10") (pin "5") (pinfunction "+IN_5") (pintype "input"))
      (node (ref "IC7") (pin "7") (pinfunction "OUT_7") (pintype "output"))
      (node (ref "R62") (pin "2") (pinfunction "2_2") (pintype "passive"))
    )
    (net (code "81") (name "Net-(IC10B--IN)") (class "Default")
      (node (ref "IC10") (pin "6") (pinfunction "-IN_6") (pintype "input"))
      (node (ref "LED9") (pin "2") (pinfunction "2_2") (pintype "bidirectional"))
      (node (ref "R78") (pin "1") (pinfunction "1_1") (pintype "passive"))
    )
    (net (code "82") (name "Net-(IC10B-OUT)") (class "Default")
      (node (ref "IC10") (pin "7") (pinfunction "OUT_7") (pintype "output"))
      (node (ref "LED9") (pin "1") (pinfunction "1_1") (pintype "bidirectional"))
    )
    (net (code "83") (name "Net-(IC10C-+IN)") (class "Default")
      (node (ref "C44") (pin "2") (pinfunction "2_2") (pintype "passive"))
      (node (ref "IC10") (pin "10") (pinfunction "+IN_10") (pintype "input"))
      (node (ref "IC7") (pin "8") (pinfunction "OUT_8") (pintype "output"))
      (node (ref "R63") (pin "2") (pinfunction "2_2") (pintype "passive"))
    )
    (net (code "84") (name "Net-(IC10C--IN)") (class "Default")
      (node (ref "IC10") (pin "9") (pinfunction "-IN_9") (pintype "input"))
      (node (ref "LED12") (pin "2") (pinfunction "2_2") (pintype "bidirectional"))
      (node (ref "R81") (pin "1") (pinfunction "1_1") (pintype "passive"))
    )
    (net (code "85") (name "Net-(IC10C-OUT)") (class "Default")
      (node (ref "IC10") (pin "8") (pinfunction "OUT_8") (pintype "output"))
      (node (ref "LED12") (pin "1") (pinfunction "1_1") (pintype "bidirectional"))
    )
    (net (code "86") (name "Net-(IC10D-+IN)") (class "Default")
      (node (ref "C35") (pin "2") (pinfunction "2_2") (pintype "passive"))
      (node (ref "IC10") (pin "12") (pinfunction "+IN_12") (pintype "input"))
      (node (ref "IC7") (pin "14") (pinfunction "OUT_14") (pintype "output"))
      (node (ref "R46") (pin "2") (pinfunction "2_2") (pintype "passive"))
    )
    (net (code "87") (name "Net-(IC10D--IN)") (class "Default")
      (node (ref "IC10") (pin "13") (pinfunction "-IN_13") (pintype "input"))
      (node (ref "LED11") (pin "2") (pinfunction "2_2") (pintype "bidirectional"))
      (node (ref "R80") (pin "1") (pinfunction "1_1") (pintype "passive"))
    )
    (net (code "88") (name "Net-(IC10D-OUT)") (class "Default")
      (node (ref "IC10") (pin "14") (pinfunction "OUT_14") (pintype "output"))
      (node (ref "LED11") (pin "1") (pinfunction "1_1") (pintype "bidirectional"))
    )
    (net (code "89") (name "Net-(J1-3)") (class "Default")
      (node (ref "C53") (pin "1") (pinfunction "1_1") (pintype "passive"))
      (node (ref "J1") (pin "P3") (pinfunction "3_P3") (pintype "passive"))
      (node (ref "R64") (pin "2") (pinfunction "2_2") (pintype "passive"))
    )
    (net (code "90") (name "Net-(J2-3)") (class "Default")
      (node (ref "C45") (pin "1") (pinfunction "1_1") (pintype "passive"))
      (node (ref "J2") (pin "P3") (pinfunction "3_P3") (pintype "passive"))
      (node (ref "R33") (pin "2") (pinfunction "2_2") (pintype "passive"))
    )
    (net (code "91") (name "Net-(J3-2)") (class "Default")
      (node (ref "J3") (pin "P2") (pinfunction "2_P2") (pintype "passive"))
      (node (ref "R76") (pin "2") (pinfunction "2_2") (pintype "passive"))
    )
    (net (code "92") (name "Net-(J3-3)") (class "Default")
      (node (ref "J3") (pin "P3") (pinfunction "3_P3") (pintype "passive"))
      (node (ref "R26") (pin "1") (pinfunction "1_1") (pintype "passive"))
    )
    (net (code "93") (name "Net-(J4-3)") (class "Default")
      (node (ref "C56") (pin "1") (pinfunction "1_1") (pintype "passive"))
      (node (ref "J4") (pin "P3") (pinfunction "3_P3") (pintype "passive"))
      (node (ref "R65") (pin "2") (pinfunction "2_2") (pintype "passive"))
    )
    (net (code "94") (name "Net-(J5-3)") (class "Default")
      (node (ref "C58") (pin "1") (pinfunction "1_1") (pintype "passive"))
      (node (ref "J5") (pin "P3") (pinfunction "3_P3") (pintype "passive"))
      (node (ref "R66") (pin "2") (pinfunction "2_2") (pintype "passive"))
    )
    (net (code "95") (name "Net-(J6-3)") (class "Default")
      (node (ref "C54") (pin "1") (pinfunction "1_1") (pintype "passive"))
      (node (ref "J6") (pin "P3") (pinfunction "3_P3") (pintype "passive"))
      (node (ref "R32") (pin "2") (pinfunction "2_2") (pintype "passive"))
    )
    (net (code "96") (name "Net-(J7-3)") (class "Default")
      (node (ref "C55") (pin "1") (pinfunction "1_1") (pintype "passive"))
      (node (ref "J7") (pin "P3") (pinfunction "3_P3") (pintype "passive"))
      (node (ref "R35") (pin "2") (pinfunction "2_2") (pintype "passive"))
    )
    (net (code "97") (name "Net-(J8-3)") (class "Default")
      (node (ref "C57") (pin "1") (pinfunction "1_1") (pintype "passive"))
      (node (ref "J8") (pin "P3") (pinfunction "3_P3") (pintype "passive"))
      (node (ref "R34") (pin "2") (pinfunction "2_2") (pintype "passive"))
    )
    (net (code "98") (name "Net-(J9-2)") (class "Default")
      (node (ref "J9") (pin "P2") (pinfunction "2_P2") (pintype "passive"))
      (node (ref "R77") (pin "2") (pinfunction "2_2") (pintype "passive"))
    )
    (net (code "99") (name "Net-(J9-3)") (class "Default")
      (node (ref "J9") (pin "P3") (pinfunction "3_P3") (pintype "passive"))
      (node (ref "R27") (pin "1") (pinfunction "1_1") (pintype "passive"))
    )
    (net (code "100") (name "Net-(J10-3)") (class "Default")
      (node (ref "J10") (pin "P3") (pinfunction "3_P3") (pintype "passive"))
      (node (ref "R85") (pin "1") (pinfunction "1_1") (pintype "passive"))
    )
    (net (code "101") (name "Net-(J11-3)") (class "Default")
      (node (ref "J11") (pin "P3") (pinfunction "3_P3") (pintype "passive"))
      (node (ref "R86") (pin "1") (pinfunction "1_1") (pintype "passive"))
    )
    (net (code "102") (name "Net-(J12-3)") (class "Default")
      (node (ref "J12") (pin "P3") (pinfunction "3_P3") (pintype "passive"))
      (node (ref "R87") (pin "1") (pinfunction "1_1") (pintype "passive"))
    )
    (net (code "103") (name "Net-(J13-3)") (class "Default")
      (node (ref "J13") (pin "P3") (pinfunction "3_P3") (pintype "passive"))
      (node (ref "R60") (pin "1") (pinfunction "1_1") (pintype "passive"))
      (node (ref "R62") (pin "1") (pinfunction "1_1") (pintype "passive"))
    )
    (net (code "104") (name "Net-(J14-3)") (class "Default")
      (node (ref "J14") (pin "P3") (pinfunction "3_P3") (pintype "passive"))
      (node (ref "R43") (pin "1") (pinfunction "1_1") (pintype "passive"))
      (node (ref "R45") (pin "1") (pinfunction "1_1") (pintype "passive"))
    )
    (net (code "105") (name "Net-(J15-3)") (class "Default")
      (node (ref "J15") (pin "P3") (pinfunction "3_P3") (pintype "passive"))
      (node (ref "R44") (pin "1") (pinfunction "1_1") (pintype "passive"))
      (node (ref "R46") (pin "1") (pinfunction "1_1") (pintype "passive"))
    )
    (net (code "106") (name "Net-(J16-3)") (class "Default")
      (node (ref "J16") (pin "P3") (pinfunction "3_P3") (pintype "passive"))
      (node (ref "R61") (pin "1") (pinfunction "1_1") (pintype "passive"))
      (node (ref "R63") (pin "1") (pinfunction "1_1") (pintype "passive"))
    )
    (net (code "107") (name "Net-(JP2-Pad1)") (class "Default")
      (node (ref "JP2") (pin "1") (pinfunction "1_1") (pintype "passive"))
      (node (ref "R3") (pin "1") (pinfunction "1_1") (pintype "passive"))
    )
    (net (code "108") (name "Net-(JP2-Pad2)") (class "Default")
      (node (ref "JP2") (pin "2") (pinfunction "2_2") (pintype "passive"))
      (node (ref "R2") (pin "1") (pinfunction "1_1") (pintype "passive"))
    )
    (net (code "109") (name "Net-(LED1-GRN)") (class "Default")
      (node (ref "LED1") (pin "1") (pinfunction "GRN_1") (pintype "bidirectional"))
      (node (ref "R10") (pin "2") (pinfunction "2_2") (pintype "passive"))
    )
    (net (code "110") (name "Net-(LED1-RED)") (class "Default")
      (node (ref "LED1") (pin "3") (pinfunction "RED_3") (pintype "bidirectional"))
      (node (ref "R9") (pin "2") (pinfunction "2_2") (pintype "passive"))
    )
    (net (code "111") (name "Net-(LED2-GRN)") (class "Default")
      (node (ref "LED2") (pin "1") (pinfunction "GRN_1") (pintype "bidirectional"))
      (node (ref "R12") (pin "2") (pinfunction "2_2") (pintype "passive"))
    )
    (net (code "112") (name "Net-(LED2-RED)") (class "Default")
      (node (ref "LED2") (pin "3") (pinfunction "RED_3") (pintype "bidirectional"))
      (node (ref "R11") (pin "2") (pinfunction "2_2") (pintype "passive"))
    )
    (net (code "113") (name "Net-(LED3-GRN)") (class "Default")
      (node (ref "LED3") (pin "1") (pinfunction "GRN_1") (pintype "bidirectional"))
      (node (ref "R18") (pin "2") (pinfunction "2_2") (pintype "passive"))
    )
    (net (code "114") (name "Net-(LED3-RED)") (class "Default")
      (node (ref "LED3") (pin "3") (pinfunction "RED_3") (pintype "bidirectional"))
      (node (ref "R19") (pin "2") (pinfunction "2_2") (pintype "passive"))
    )
    (net (code "115") (name "Net-(LED4-GRN)") (class "Default")
      (node (ref "LED4") (pin "1") (pinfunction "GRN_1") (pintype "bidirectional"))
      (node (ref "R17") (pin "2") (pinfunction "2_2") (pintype "passive"))
    )
    (net (code "116") (name "Net-(LED4-RED)") (class "Default")
      (node (ref "LED4") (pin "3") (pinfunction "RED_3") (pintype "bidirectional"))
      (node (ref "R15") (pin "2") (pinfunction "2_2") (pintype "passive"))
    )
    (net (code "117") (name "Net-(LED5-GRN)") (class "Default")
      (node (ref "LED5") (pin "1") (pinfunction "GRN_1") (pintype "bidirectional"))
      (node (ref "R36") (pin "2") (pinfunction "2_2") (pintype "passive"))
    )
    (net (code "118") (name "Net-(LED6-Pad2)") (class "Default")
      (node (ref "LED6") (pin "2") (pinfunction "2_2") (pintype "bidirectional"))
      (node (ref "R82") (pin "2") (pinfunction "2_2") (pintype "passive"))
    )
    (net (code "119") (name "Net-(LED7-Pad2)") (class "Default")
      (node (ref "LED7") (pin "2") (pinfunction "2_2") (pintype "bidirectional"))
      (node (ref "R83") (pin "2") (pinfunction "2_2") (pintype "passive"))
    )
    (net (code "120") (name "Net-(LED8-Pad2)") (class "Default")
      (node (ref "LED8") (pin "2") (pinfunction "2_2") (pintype "bidirectional"))
      (node (ref "R84") (pin "2") (pinfunction "2_2") (pintype "passive"))
    )
    (net (code "121") (name "Net-(Q1B-2)") (class "Default")
      (node (ref "C4") (pin "2") (pinfunction "2_2") (pintype "passive"))
      (node (ref "Q1") (pin "3") (pinfunction "2_3") (pintype "passive"))
      (node (ref "R8") (pin "2") (pinfunction "2_2") (pintype "passive"))
    )
    (net (code "122") (name "Net-(R1-Pad2)") (class "Default")
      (node (ref "R1") (pin "2") (pinfunction "2_2") (pintype "passive"))
      (node (ref "SW1") (pin "L1") (pinfunction "L1_L1") (pintype "passive"))
    )
    (net (code "123") (name "Net-(R5-Pad2)") (class "Default")
      (node (ref "R5") (pin "2") (pinfunction "2_2") (pintype "passive"))
      (node (ref "SW2") (pin "L1") (pinfunction "L1_L1") (pintype "passive"))
    )
    (net (code "124") (name "RESET") (class "Default")
      (node (ref "C7") (pin "1") (pinfunction "1_1") (pintype "passive"))
      (node (ref "IC2") (pin "7") (pinfunction "NRST_7") (pintype "bidirectional"))
      (node (ref "JP1") (pin "4") (pinfunction "4_4") (pintype "passive"))
      (node (ref "R6") (pin "1") (pinfunction "1_1") (pintype "passive"))
      (node (ref "U1") (pin "2") (pinfunction "~{RESET}_2") (pintype "passive"))
    )
    (net (code "125") (name "RX") (class "Default")
      (node (ref "IC2") (pin "43") (pinfunction "PA10/USART1_RX/TIM1_CH3_43") (pintype "bidirectional"))
      (node (ref "R3") (pin "2") (pinfunction "2_2") (pintype "passive"))
    )
    (net (code "126") (name "SWCLK") (class "Default")
      (node (ref "IC2") (pin "49") (pinfunction "PA14/JTCK-SWCLK_49") (pintype "bidirectional"))
      (node (ref "JP1") (pin "3") (pinfunction "3_3") (pintype "passive"))
    )
    (net (code "127") (name "SWDIO") (class "Default")
      (node (ref "IC2") (pin "46") (pinfunction "PA13/JTMS-SWDAT_46") (pintype "bidirectional"))
      (node (ref "JP1") (pin "2") (pinfunction "2_2") (pintype "passive"))
    )
    (net (code "128") (name "SW_T_DV") (class "Default")
      (node (ref "IC2") (pin "30") (pinfunction "PB11/I2C2_SDA/USART3_RX_30") (pintype "bidirectional"))
      (node (ref "SW1") (pin "P2") (pinfunction "A2_P2") (pintype "passive"))
      (node (ref "SW1") (pin "P5") (pinfunction "B2_P5") (pintype "passive"))
    )
    (net (code "129") (name "SW_T_MODE") (class "Default")
      (node (ref "IC2") (pin "35") (pinfunction "PB14/SPI2_MISO/USART3_RTS/TIM1_CH2N_35") (pintype "bidirectional"))
      (node (ref "SW3") (pin "3") (pinfunction "3_3") (pintype "passive"))
      (node (ref "SW3") (pin "4") (pinfunction "4_4") (pintype "passive"))
    )
    (net (code "130") (name "SW_T_RANGE") (class "Default")
      (node (ref "IC2") (pin "36") (pinfunction "PB15/SPI2_MOSI/I2S2_SD/TIM1_CH3N_36") (pintype "bidirectional"))
      (node (ref "SW5") (pin "3") (pinfunction "3_3") (pintype "passive"))
      (node (ref "SW5") (pin "4") (pinfunction "4_4") (pintype "passive"))
    )
    (net (code "131") (name "SW_X_DV") (class "Default")
      (node (ref "IC2") (pin "4") (pinfunction "PC15/OSC_OUT_4") (pintype "bidirectional"))
      (node (ref "SW2") (pin "P2") (pinfunction "A2_P2") (pintype "passive"))
      (node (ref "SW2") (pin "P5") (pinfunction "B2_P5") (pintype "passive"))
    )
    (net (code "132") (name "SW_X_EXT") (class "Default")
      (node (ref "IC2") (pin "54") (pinfunction "PD2/TIM3-ETR_54") (pintype "bidirectional"))
      (node (ref "SW7") (pin "3") (pinfunction "3_3") (pintype "passive"))
      (node (ref "SW7") (pin "4") (pinfunction "4_4") (pintype "passive"))
    )
    (net (code "133") (name "SW_X_MODE") (class "Default")
      (node (ref "IC2") (pin "2") (pinfunction "PC13-TAMPER-RTC_2") (pintype "bidirectional"))
      (node (ref "SW4") (pin "3") (pinfunction "3_3") (pintype "passive"))
      (node (ref "SW4") (pin "4") (pinfunction "4_4") (pintype "passive"))
    )
    (net (code "134") (name "SW_X_RANGE") (class "Default")
      (node (ref "IC2") (pin "58") (pinfunction "PB6/I2C1_SCL/TIM4_CH1/USART1_TX_58") (pintype "bidirectional"))
      (node (ref "SW6") (pin "3") (pinfunction "3_3") (pintype "passive"))
      (node (ref "SW6") (pin "4") (pinfunction "4_4") (pintype "passive"))
    )
    (net (code "135") (name "TX") (class "Default")
      (node (ref "IC2") (pin "42") (pinfunction "PA9/USART1_TX/TIM1_CH2_42") (pintype "bidirectional"))
      (node (ref "R2") (pin "2") (pinfunction "2_2") (pintype "passive"))
    )
    (net (code "136") (name "T_CLOCK") (class "Default")
      (node (ref "IC2") (pin "40") (pinfunction "PC9/I2S2_CKIN/I2S3_CKIN_40") (pintype "bidirectional"))
      (node (ref "Q2") (pin "C") (pinfunction "C_C") (pintype "passive"))
      (node (ref "R22") (pin "1") (pinfunction "1_1") (pintype "passive"))
    )
    (net (code "137") (name "VCC") (class "Default")
      (node (ref "C11") (pin "+") (pinfunction "+_+") (pintype "passive"))
      (node (ref "C39") (pin "1") (pinfunction "1_1") (pintype "passive"))
      (node (ref "C48") (pin "1") (pinfunction "1_1") (pintype "passive"))
      (node (ref "C50") (pin "1") (pinfunction "1_1") (pintype "passive"))
      (node (ref "IC10") (pin "4") (pinfunction "V+_4") (pintype "power_in"))
      (node (ref "IC7") (pin "4") (pinfunction "V+_4") (pintype "power_in"))
      (node (ref "IC9") (pin "4") (pinfunction "V+_4") (pintype "power_in"))
      (node (ref "L2") (pin "1") (pinfunction "1_1") (pintype "passive"))
    )
    (net (code "138") (name "VEE") (class "Default")
      (node (ref "C22") (pin "-") (pinfunction "-_-") (pintype "passive"))
      (node (ref "C37") (pin "2") (pinfunction "2_2") (pintype "passive"))
      (node (ref "C49") (pin "2") (pinfunction "2_2") (pintype "passive"))
      (node (ref "IC10") (pin "11") (pinfunction "V-_11") (pintype "power_in"))
      (node (ref "IC7") (pin "11") (pinfunction "V-_11") (pintype "power_in"))
      (node (ref "L4") (pin "1") (pinfunction "1_1") (pintype "passive"))
      (node (ref "R68") (pin "1") (pinfunction "1_1") (pintype "passive"))
    )
    (net (code "139") (name "VREF") (class "Default")
      (node (ref "C25") (pin "1") (pinfunction "1_1") (pintype "passive"))
      (node (ref "IC4") (pin "3") (pinfunction "VREFH_3") (pintype "bidirectional"))
      (node (ref "R74") (pin "2") (pinfunction "2_2") (pintype "passive"))
    )
    (net (code "140") (name "VREF_BIAS") (class "Default")
      (node (ref "C51") (pin "1") (pinfunction "1_1") (pintype "passive"))
      (node (ref "IC7") (pin "10") (pinfunction "+IN_10") (pintype "input"))
      (node (ref "IC7") (pin "12") (pinfunction "+IN_12") (pintype "input"))
      (node (ref "IC7") (pin "3") (pinfunction "+IN_3") (pintype "input"))
      (node (ref "IC7") (pin "5") (pinfunction "+IN_5") (pintype "input"))
      (node (ref "R73") (pin "2") (pinfunction "2_2") (pintype "passive"))
      (node (ref "R74") (pin "1") (pinfunction "1_1") (pintype "passive"))
    )
    (net (code "141") (name "X_CLOCK") (class "Default")
      (node (ref "IC2") (pin "41") (pinfunction "PA8/USART1_CK/TIM1_CH1/MCO_41") (pintype "bidirectional"))
      (node (ref "Q3") (pin "C") (pinfunction "C_C") (pintype "passive"))
      (node (ref "R23") (pin "1") (pinfunction "1_1") (pintype "passive"))
    )
    (net (code "142") (name "unconnected-(IC2-PC14{slash}OSC32_IN-Pad3)") (class "Default")
      (node (ref "IC2") (pin "3") (pinfunction "PC14/OSC32_IN_3") (pintype "bidirectional"))
    )
    (net (code "143") (name "unconnected-(J10-2-PadP2)") (class "Default")
      (node (ref "J10") (pin "P2") (pinfunction "2_P2") (pintype "passive"))
    )
    (net (code "144") (name "unconnected-(J11-2-PadP2)") (class "Default")
      (node (ref "J11") (pin "P2") (pinfunction "2_P2") (pintype "passive"))
    )
    (net (code "145") (name "unconnected-(J12-2-PadP2)") (class "Default")
      (node (ref "J12") (pin "P2") (pinfunction "2_P2") (pintype "passive"))
    )
    (net (code "146") (name "unconnected-(J13-2-PadP2)") (class "Default")
      (node (ref "J13") (pin "P2") (pinfunction "2_P2") (pintype "passive"))
    )
    (net (code "147") (name "unconnected-(J14-2-PadP2)") (class "Default")
      (node (ref "J14") (pin "P2") (pinfunction "2_P2") (pintype "passive"))
    )
    (net (code "148") (name "unconnected-(J15-2-PadP2)") (class "Default")
      (node (ref "J15") (pin "P2") (pinfunction "2_P2") (pintype "passive"))
    )
    (net (code "149") (name "unconnected-(J16-2-PadP2)") (class "Default")
      (node (ref "J16") (pin "P2") (pinfunction "2_P2") (pintype "passive"))
    )
    (net (code "150") (name "unconnected-(LED5-RED-Pad3)") (class "Default")
      (node (ref "LED5") (pin "3") (pinfunction "RED_3") (pintype "bidirectional"))
    )
    (net (code "151") (name "unconnected-(SW1A-A1-PadP1)") (class "Default")
      (node (ref "SW1") (pin "P1") (pinfunction "A1_P1") (pintype "passive"))
    )
    (net (code "152") (name "unconnected-(SW1A-B1-PadP4)") (class "Default")
      (node (ref "SW1") (pin "P4") (pinfunction "B1_P4") (pintype "passive"))
    )
    (net (code "153") (name "unconnected-(SW2A-A1-PadP1)") (class "Default")
      (node (ref "SW2") (pin "P1") (pinfunction "A1_P1") (pintype "passive"))
    )
    (net (code "154") (name "unconnected-(SW2A-B1-PadP4)") (class "Default")
      (node (ref "SW2") (pin "P4") (pinfunction "B1_P4") (pintype "passive"))
    )
  )
)
